# controller.net
KiCad netlist of a schematic drawn in EAGLE
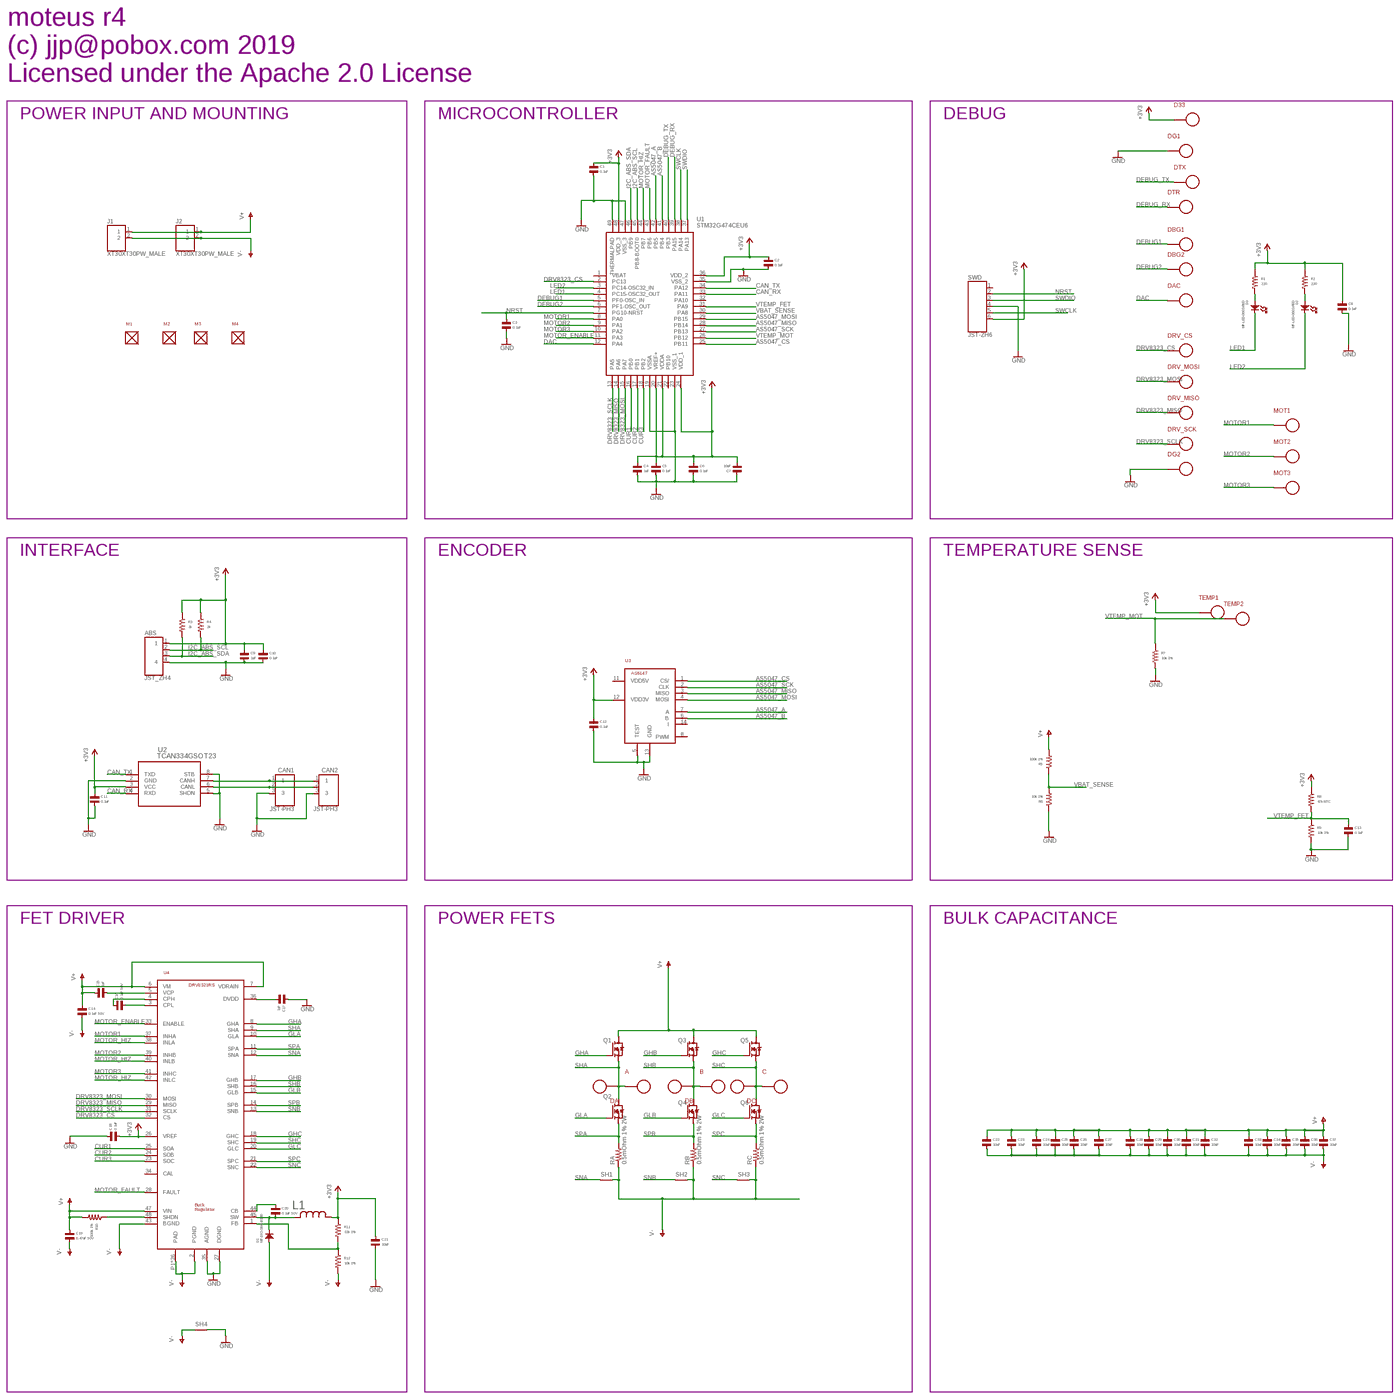
[diagram p0: schematic, sheet 1, overview]
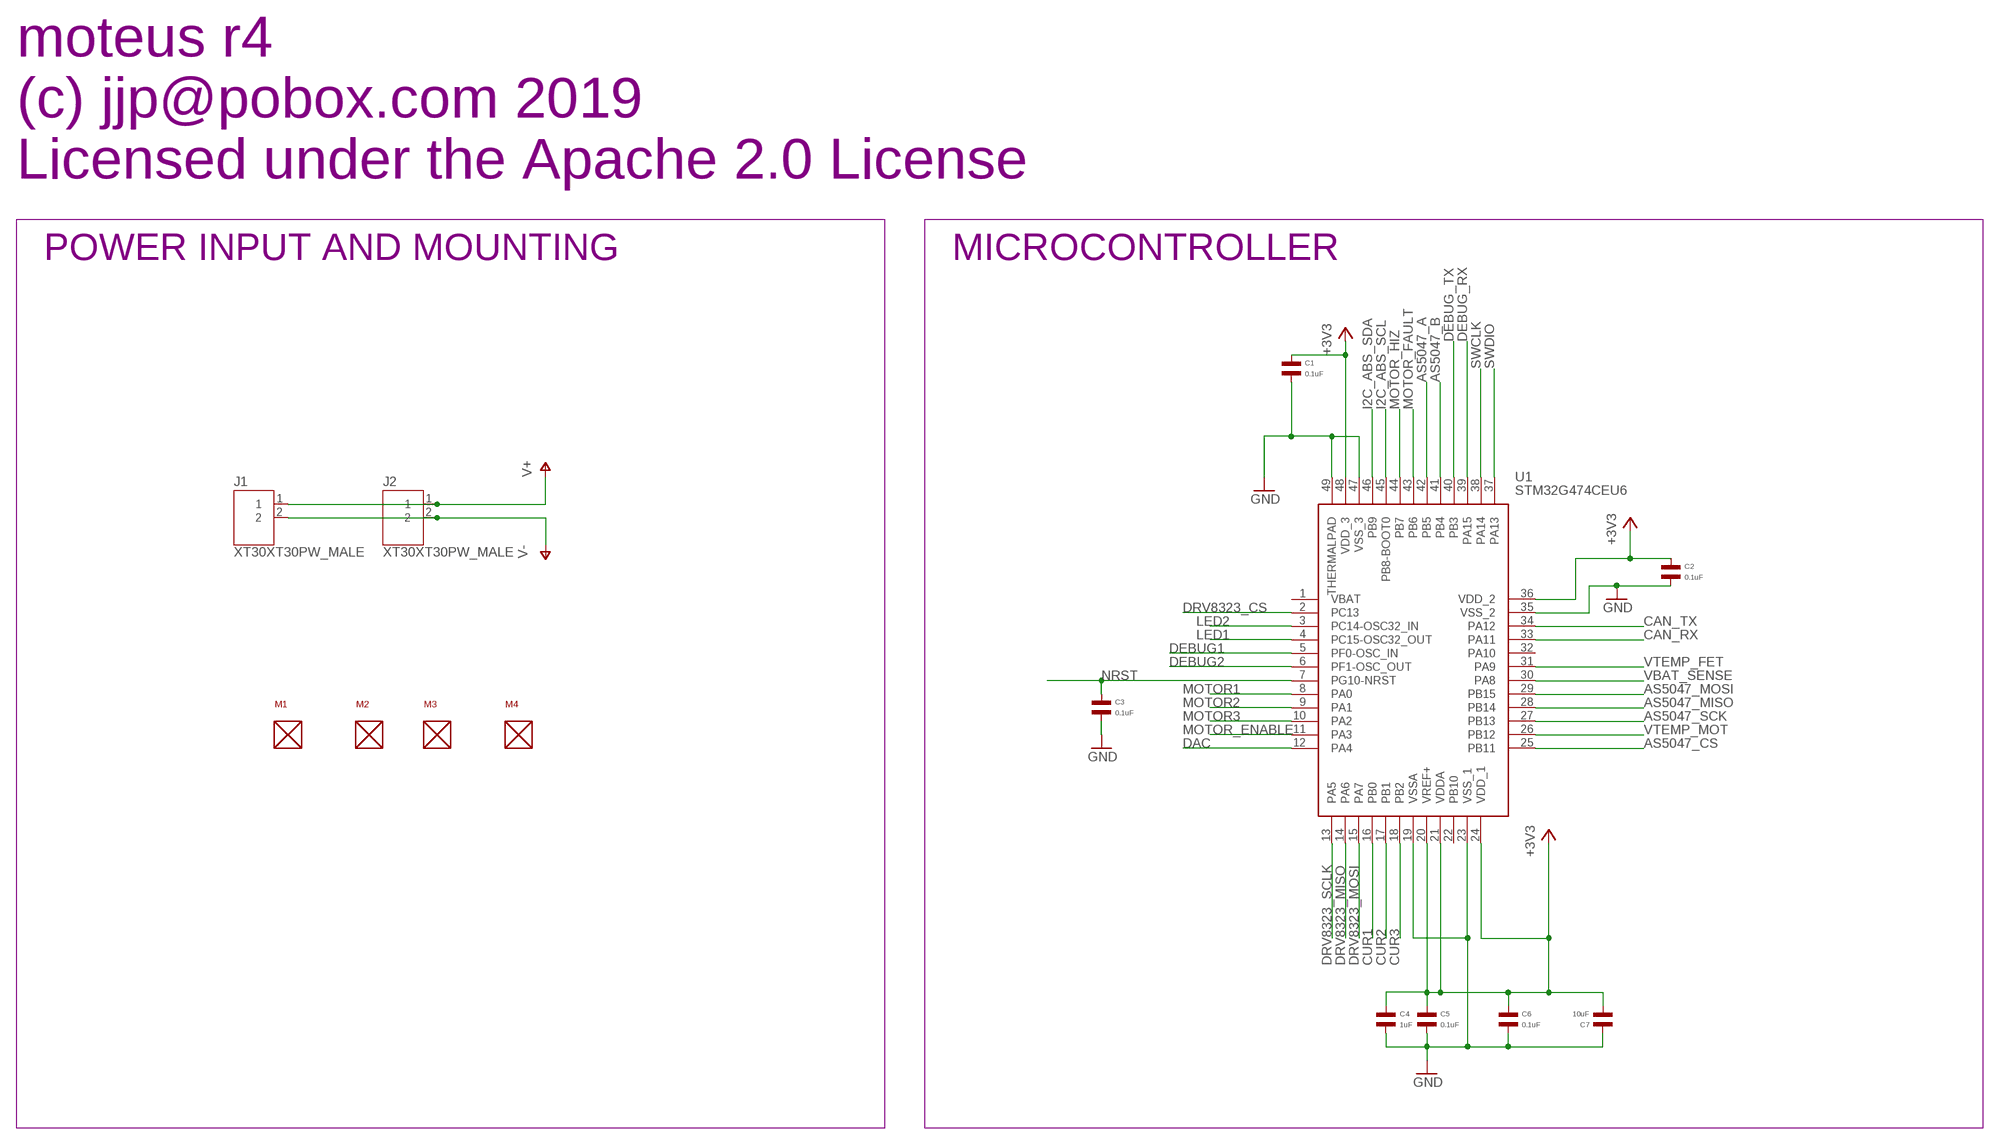
[diagram p1: schematic, sheet 1, part 1 of 4]
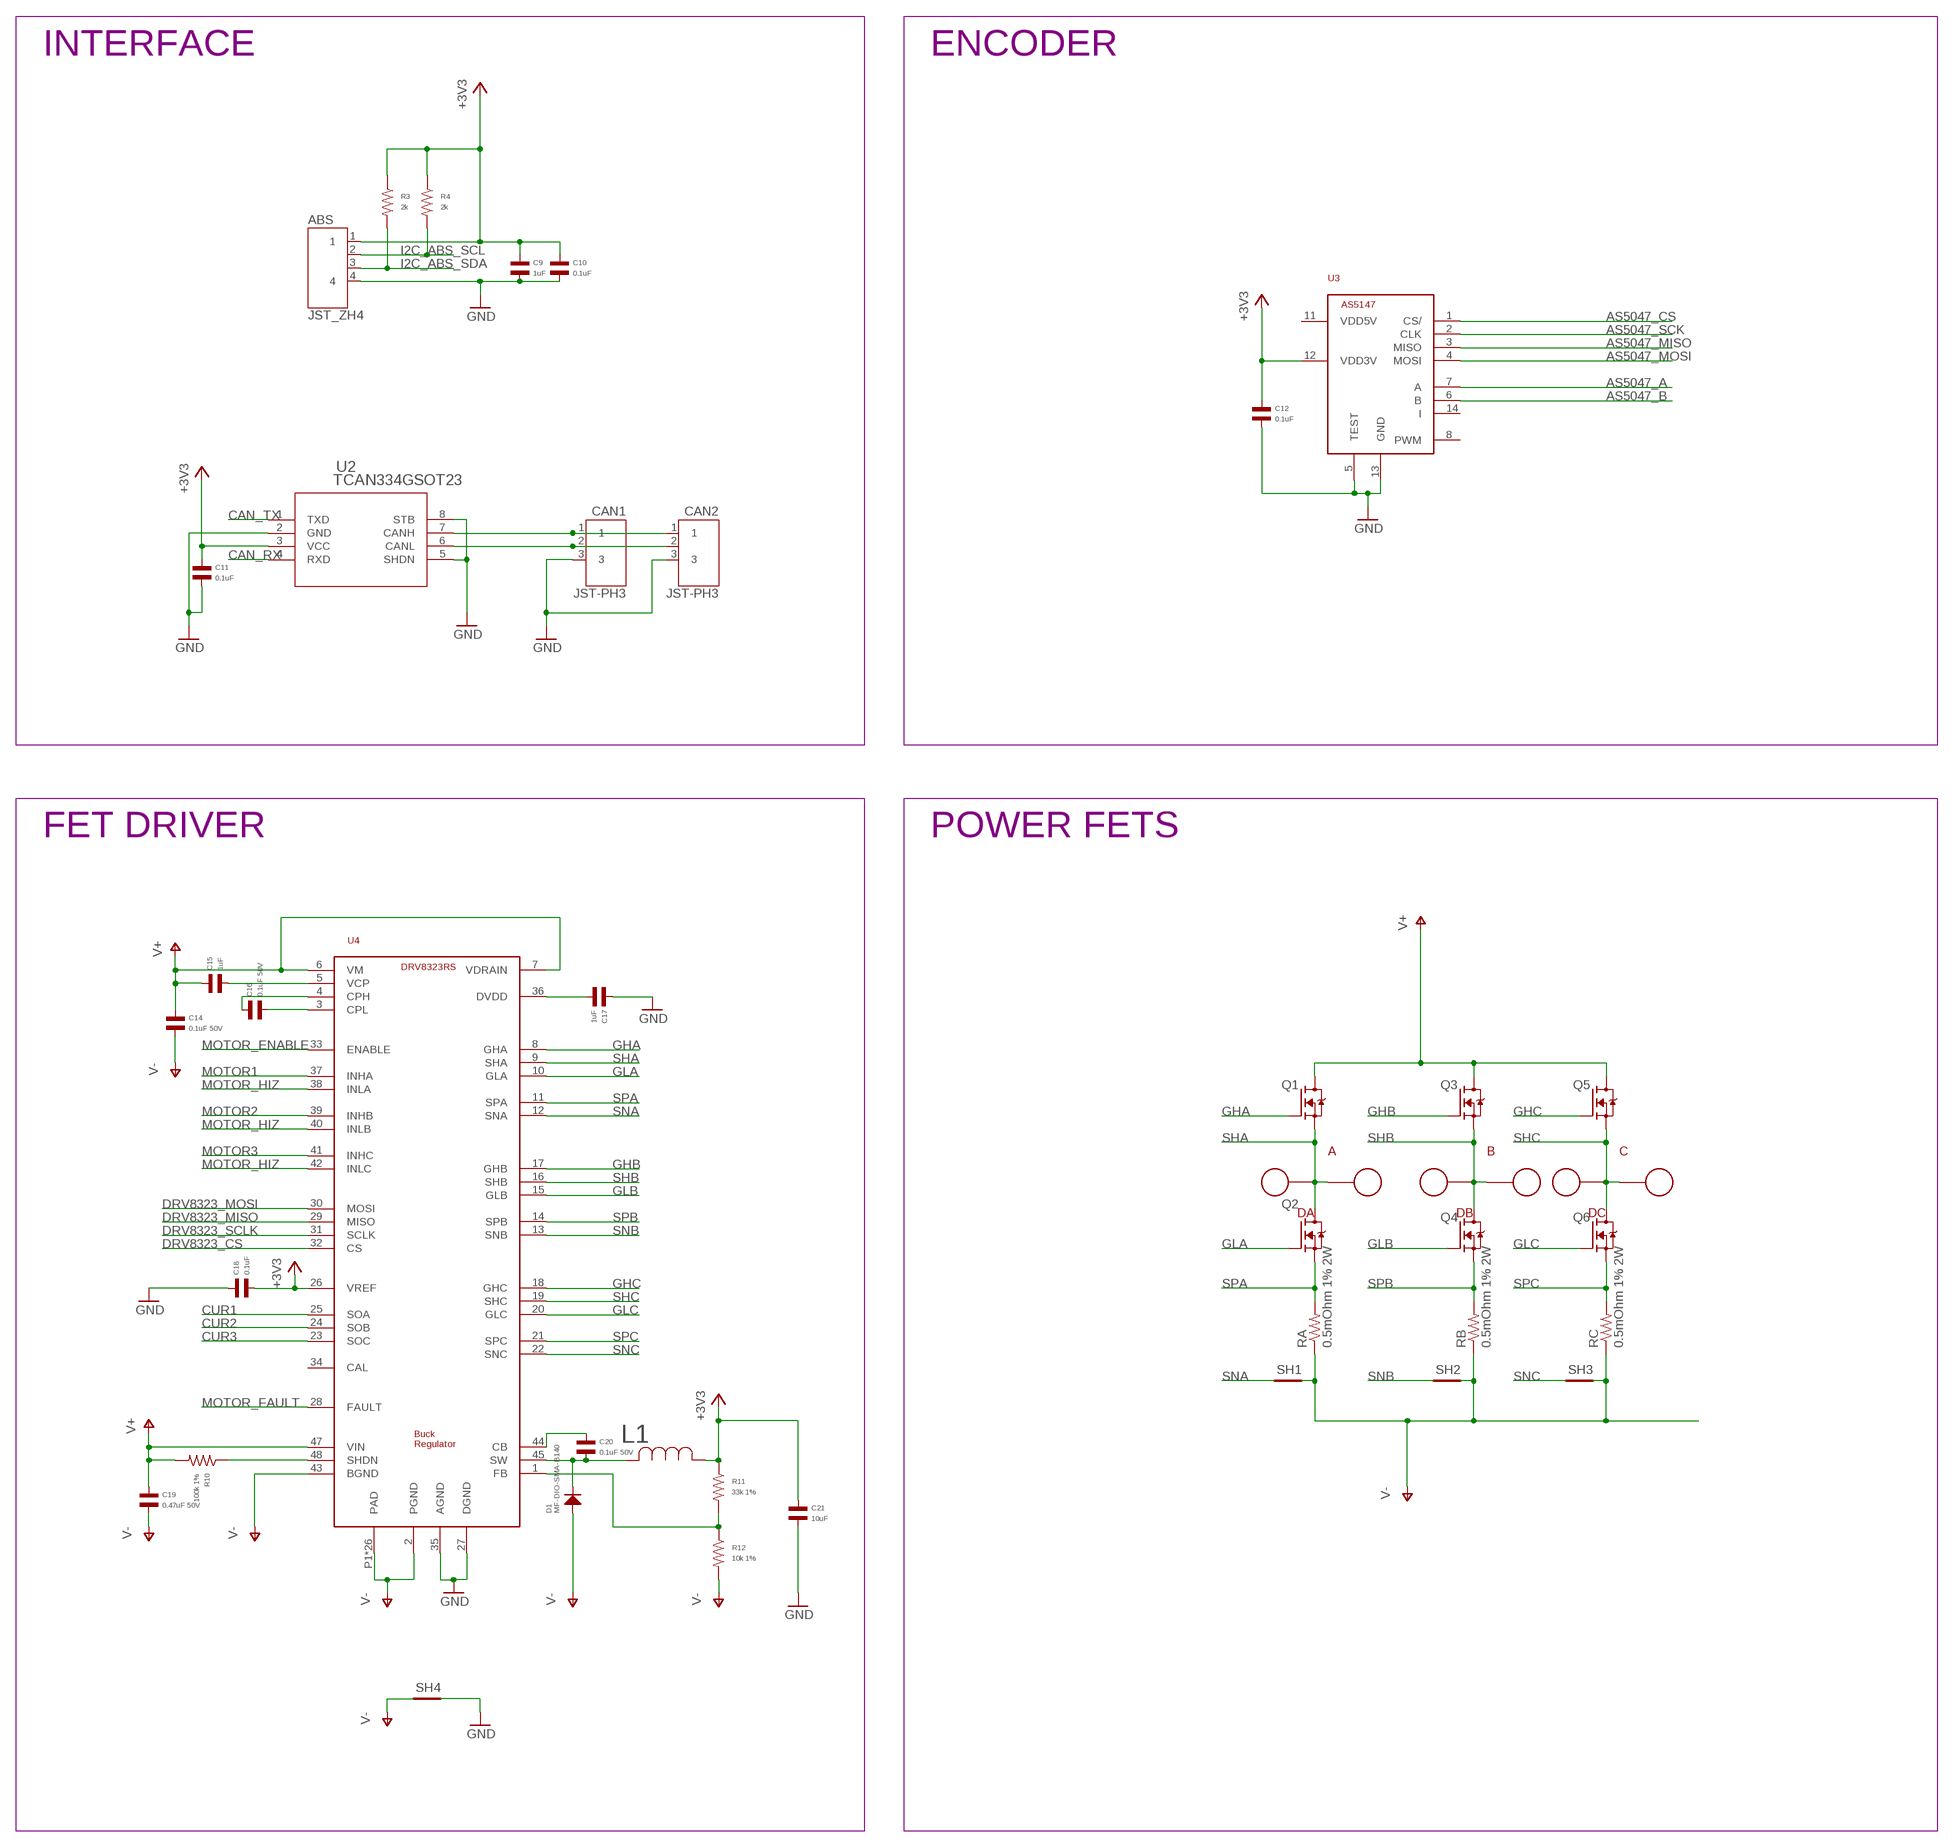
[diagram p2: schematic, sheet 1, part 2 of 4]
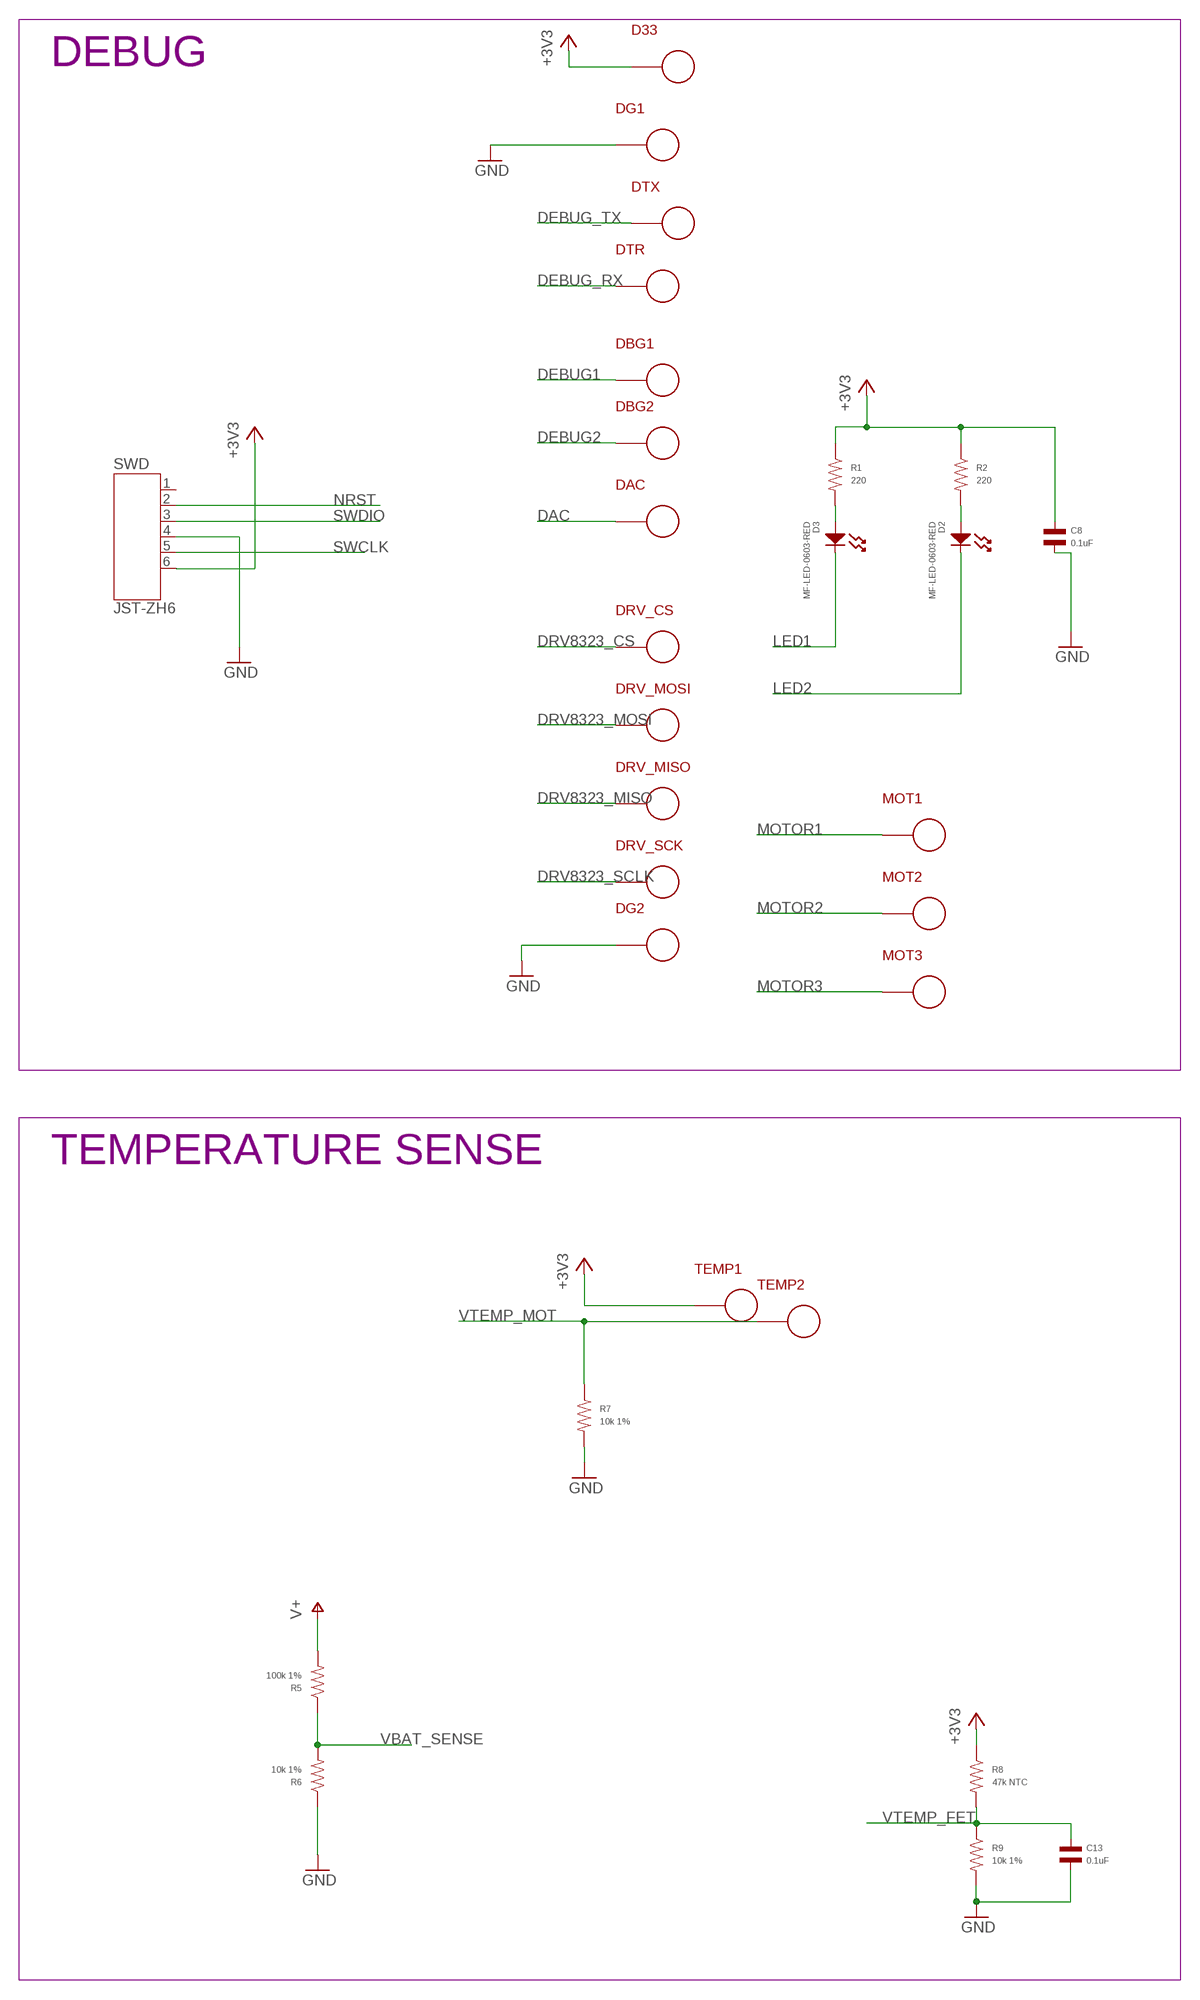
[diagram p3: schematic, sheet 1, part 3 of 4]
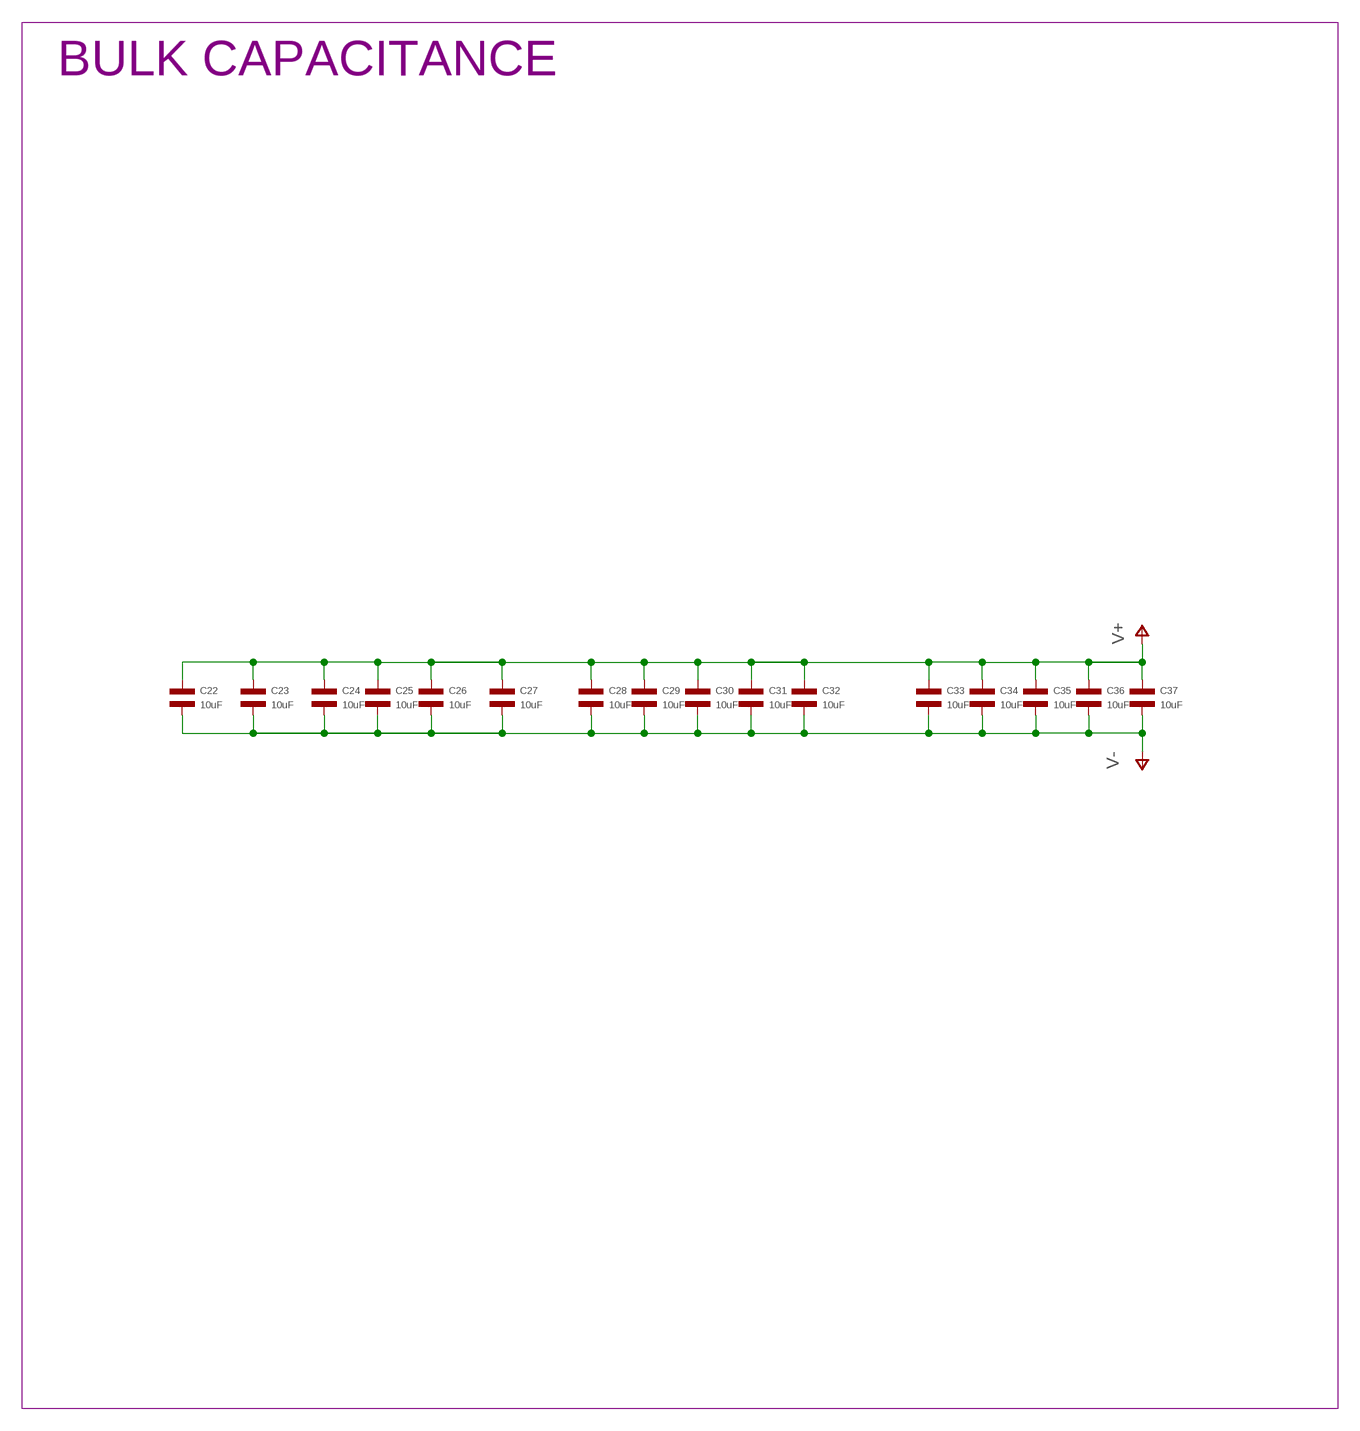
[diagram p4: schematic, sheet 1, part 4 of 4]

(export (version "E")
  (design (tool "Eeschema 10.0.6"))
  (components
    (comp (ref "A")
      (value "PAD")
      (footprint "eagle-import:18AWG_PAD")
      (libsource (lib "eagle-import") (part "PAD"))
    )
    (comp (ref "ABS")
      (value "JST_ZH4")
      (footprint "eagle-import:JST_S4B-ZR-SM4A-TF(LF)(SN)")
      (fields (field (name "MF") "JST") (field (name "MPN") "S4B-ZR-SM4A-TF(LF)(SN)"))
      (libsource (lib "eagle-import") (part "JST_ZH4"))
    )
    (comp (ref "B")
      (value "PAD")
      (footprint "eagle-import:18AWG_PAD")
      (libsource (lib "eagle-import") (part "PAD"))
    )
    (comp (ref "C")
      (value "PAD")
      (footprint "eagle-import:18AWG_PAD")
      (libsource (lib "eagle-import") (part "PAD"))
    )
    (comp (ref "C1")
      (value "0.1uF")
      (footprint "eagle-import:C0402")
      (fields (field (name "HOUSEPART") "YES") (field (name "MPN") "MF-CAP-0402-0.1uF"))
      (libsource (lib "eagle-import") (part "CAPACITOR_NP_0402"))
    )
    (comp (ref "C2")
      (value "0.1uF")
      (footprint "eagle-import:C0402")
      (fields (field (name "HOUSEPART") "YES") (field (name "MPN") "MF-CAP-0402-0.1uF"))
      (libsource (lib "eagle-import") (part "CAPACITOR_NP_0402"))
    )
    (comp (ref "C3")
      (value "0.1uF")
      (footprint "eagle-import:C0402")
      (fields (field (name "HOUSEPART") "YES") (field (name "MPN") "MF-CAP-0402-0.1uF"))
      (libsource (lib "eagle-import") (part "CAPACITOR_NP_0402"))
    )
    (comp (ref "C4")
      (value "1uF")
      (footprint "eagle-import:C0402")
      (fields (field (name "HOUSEPART") "YES") (field (name "MPN") "MF-CAP-0402-1uF"))
      (libsource (lib "eagle-import") (part "CAPACITOR_NP_0402"))
    )
    (comp (ref "C5")
      (value "0.1uF")
      (footprint "eagle-import:C0402")
      (fields (field (name "HOUSEPART") "YES") (field (name "MPN") "MF-CAP-0402-0.1uF"))
      (libsource (lib "eagle-import") (part "CAPACITOR_NP_0402"))
    )
    (comp (ref "C6")
      (value "0.1uF")
      (footprint "eagle-import:C0402")
      (fields (field (name "HOUSEPART") "YES") (field (name "MPN") "MF-CAP-0402-0.1uF"))
      (libsource (lib "eagle-import") (part "CAPACITOR_NP_0402"))
    )
    (comp (ref "C7")
      (value "10uF")
      (footprint "eagle-import:C1206")
      (fields (field (name "HOUSEPART") "YES") (field (name "MPN") "MF-CAP-1206-10uF"))
      (libsource (lib "eagle-import") (part "CAPACITOR_NP_1206"))
    )
    (comp (ref "C8")
      (value "0.1uF")
      (footprint "eagle-import:C0402")
      (fields (field (name "HOUSEPART") "YES") (field (name "MPN") "MF-CAP-0402-0.1uF"))
      (libsource (lib "eagle-import") (part "CAPACITOR_NP_0402"))
    )
    (comp (ref "C9")
      (value "1uF")
      (footprint "eagle-import:C0402")
      (fields (field (name "HOUSEPART") "YES") (field (name "MPN") "MF-CAP-0402-1uF"))
      (libsource (lib "eagle-import") (part "CAPACITOR_NP_0402"))
    )
    (comp (ref "C10")
      (value "0.1uF")
      (footprint "eagle-import:C0402")
      (fields (field (name "HOUSEPART") "YES") (field (name "MPN") "MF-CAP-0402-0.1uF"))
      (libsource (lib "eagle-import") (part "CAPACITOR_NP_0402"))
    )
    (comp (ref "C11")
      (value "0.1uF")
      (footprint "eagle-import:C0402")
      (fields (field (name "HOUSEPART") "YES") (field (name "MPN") "MF-CAP-0402-0.1uF"))
      (libsource (lib "eagle-import") (part "CAPACITOR_NP_0402"))
    )
    (comp (ref "C12")
      (value "0.1uF")
      (footprint "eagle-import:C0402")
      (fields (field (name "HOUSEPART") "YES") (field (name "MPN") "MF-CAP-0402-0.1uF"))
      (libsource (lib "eagle-import") (part "CAPACITOR_NP_0402"))
    )
    (comp (ref "C13")
      (value "0.1uF")
      (footprint "eagle-import:C0402")
      (fields (field (name "HOUSEPART") "YES") (field (name "MPN") "MF-CAP-0402-0.1uF"))
      (libsource (lib "eagle-import") (part "CAPACITOR_NP_0402"))
    )
    (comp (ref "C14")
      (value "0.1uF 50V")
      (footprint "eagle-import:C0402")
      (fields (field (name "MF") "TDK") (field (name "MPN") "CGA2B3X7R1H104K050BB"))
      (libsource (lib "eagle-import") (part "CAPACITOR_NP_0402"))
    )
    (comp (ref "C15")
      (value "1uF")
      (footprint "eagle-import:C0402")
      (fields (field (name "HOUSEPART") "YES") (field (name "MPN") "MF-CAP-0402-1uF"))
      (libsource (lib "eagle-import") (part "CAPACITOR_NP_0402"))
    )
    (comp (ref "C16")
      (value "0.1uF 50V")
      (footprint "eagle-import:C0402")
      (fields (field (name "MF") "TDK") (field (name "MPN") "CGA2B3X7R1H104K050BB"))
      (libsource (lib "eagle-import") (part "CAPACITOR_NP_0402"))
    )
    (comp (ref "C17")
      (value "1uF")
      (footprint "eagle-import:C0402")
      (fields (field (name "HOUSEPART") "YES") (field (name "MPN") "MF-CAP-0402-1uF"))
      (libsource (lib "eagle-import") (part "CAPACITOR_NP_0402"))
    )
    (comp (ref "C18")
      (value "0.1uF")
      (footprint "eagle-import:C0402")
      (fields (field (name "HOUSEPART") "YES") (field (name "MPN") "MF-CAP-0402-0.1uF"))
      (libsource (lib "eagle-import") (part "CAPACITOR_NP_0402"))
    )
    (comp (ref "C19")
      (value "0.47uF 50V")
      (footprint "eagle-import:C0402")
      (fields (field (name "MF") "Taiyo Yuden") (field (name "MPN") "UMK105ABJ474KV-F"))
      (libsource (lib "eagle-import") (part "CAPACITOR_NP_0402"))
    )
    (comp (ref "C20")
      (value "0.1uF 50V")
      (footprint "eagle-import:C0402")
      (fields (field (name "MF") "TDK") (field (name "MPN") "CGA2B3X7R1H104K050BB"))
      (libsource (lib "eagle-import") (part "CAPACITOR_NP_0402"))
    )
    (comp (ref "C21")
      (value "10uF")
      (footprint "eagle-import:C1206")
      (fields (field (name "HOUSEPART") "YES") (field (name "MPN") "MF-CAP-1206-10uF"))
      (libsource (lib "eagle-import") (part "CAPACITOR_NP_1206"))
    )
    (comp (ref "C22")
      (value "10uF")
      (footprint "eagle-import:C1206")
      (fields (field (name "MF") "TDK") (field (name "MPN") "CGA5L1X7R1H106K160AC"))
      (libsource (lib "eagle-import") (part "CAPACITOR_NP_1206"))
    )
    (comp (ref "C23")
      (value "10uF")
      (footprint "eagle-import:C1206")
      (fields (field (name "MF") "TDK") (field (name "MPN") "CGA5L1X7R1H106K160AC"))
      (libsource (lib "eagle-import") (part "CAPACITOR_NP_1206"))
    )
    (comp (ref "C24")
      (value "10uF")
      (footprint "eagle-import:C1206")
      (fields (field (name "MF") "TDK") (field (name "MPN") "CGA5L1X7R1H106K160AC"))
      (libsource (lib "eagle-import") (part "CAPACITOR_NP_1206"))
    )
    (comp (ref "C25")
      (value "10uF")
      (footprint "eagle-import:C1206")
      (fields (field (name "MF") "TDK") (field (name "MPN") "CGA5L1X7R1H106K160AC"))
      (libsource (lib "eagle-import") (part "CAPACITOR_NP_1206"))
    )
    (comp (ref "C26")
      (value "10uF")
      (footprint "eagle-import:C1206")
      (fields (field (name "MF") "TDK") (field (name "MPN") "CGA5L1X7R1H106K160AC"))
      (libsource (lib "eagle-import") (part "CAPACITOR_NP_1206"))
    )
    (comp (ref "C27")
      (value "10uF")
      (footprint "eagle-import:C1206")
      (fields (field (name "MF") "TDK") (field (name "MPN") "CGA5L1X7R1H106K160AC"))
      (libsource (lib "eagle-import") (part "CAPACITOR_NP_1206"))
    )
    (comp (ref "C28")
      (value "10uF")
      (footprint "eagle-import:C1206")
      (fields (field (name "MF") "TDK") (field (name "MPN") "CGA5L1X7R1H106K160AC"))
      (libsource (lib "eagle-import") (part "CAPACITOR_NP_1206"))
    )
    (comp (ref "C29")
      (value "10uF")
      (footprint "eagle-import:C1206")
      (fields (field (name "MF") "TDK") (field (name "MPN") "CGA5L1X7R1H106K160AC"))
      (libsource (lib "eagle-import") (part "CAPACITOR_NP_1206"))
    )
    (comp (ref "C30")
      (value "10uF")
      (footprint "eagle-import:C1206")
      (fields (field (name "MF") "TDK") (field (name "MPN") "CGA5L1X7R1H106K160AC"))
      (libsource (lib "eagle-import") (part "CAPACITOR_NP_1206"))
    )
    (comp (ref "C31")
      (value "10uF")
      (footprint "eagle-import:C1206")
      (fields (field (name "MF") "TDK") (field (name "MPN") "CGA5L1X7R1H106K160AC"))
      (libsource (lib "eagle-import") (part "CAPACITOR_NP_1206"))
    )
    (comp (ref "C32")
      (value "10uF")
      (footprint "eagle-import:C1206")
      (fields (field (name "MF") "TDK") (field (name "MPN") "CGA5L1X7R1H106K160AC"))
      (libsource (lib "eagle-import") (part "CAPACITOR_NP_1206"))
    )
    (comp (ref "C33")
      (value "10uF")
      (footprint "eagle-import:C1206")
      (fields (field (name "MF") "TDK") (field (name "MPN") "CGA5L1X7R1H106K160AC"))
      (libsource (lib "eagle-import") (part "CAPACITOR_NP_1206"))
    )
    (comp (ref "C34")
      (value "10uF")
      (footprint "eagle-import:C1206")
      (fields (field (name "MF") "TDK") (field (name "MPN") "CGA5L1X7R1H106K160AC"))
      (libsource (lib "eagle-import") (part "CAPACITOR_NP_1206"))
    )
    (comp (ref "C35")
      (value "10uF")
      (footprint "eagle-import:C1206")
      (fields (field (name "MF") "TDK") (field (name "MPN") "CGA5L1X7R1H106K160AC"))
      (libsource (lib "eagle-import") (part "CAPACITOR_NP_1206"))
    )
    (comp (ref "C36")
      (value "10uF")
      (footprint "eagle-import:C1206")
      (fields (field (name "MF") "TDK") (field (name "MPN") "CGA5L1X7R1H106K160AC"))
      (libsource (lib "eagle-import") (part "CAPACITOR_NP_1206"))
    )
    (comp (ref "C37")
      (value "10uF")
      (footprint "eagle-import:C1206")
      (fields (field (name "MF") "TDK") (field (name "MPN") "CGA5L1X7R1H106K160AC"))
      (libsource (lib "eagle-import") (part "CAPACITOR_NP_1206"))
    )
    (comp (ref "CAN1")
      (value "JST-PH3")
      (footprint "eagle-import:JST_S3B-PH-SM4-TB(LF)(SN)")
      (fields (field (name "MF") "JST") (field (name "MPN") "S3B-PH-SM4-TB(LF)(SN)"))
      (libsource (lib "eagle-import") (part "JST-PH3"))
    )
    (comp (ref "CAN2")
      (value "JST-PH3")
      (footprint "eagle-import:JST_S3B-PH-SM4-TB(LF)(SN)")
      (fields (field (name "MF") "JST") (field (name "MPN") "S3B-PH-SM4-TB(LF)(SN)"))
      (libsource (lib "eagle-import") (part "JST-PH3"))
    )
    (comp (ref "D1")
      (value "MF-DIO-SMA-B140")
      (footprint "eagle-import:SMA")
      (fields (field (name "HOUSEPART") "YES"))
      (libsource (lib "eagle-import") (part "DIODES_SMA_B140"))
    )
    (comp (ref "D2")
      (value "MF-LED-0603-RED")
      (footprint "eagle-import:LED0603")
      (fields (field (name "HOUSEPART") "YES") (field (name "MPN") "MF-LED-0603-GREEN"))
      (libsource (lib "eagle-import") (part "LED_SINGLE-0603-RED"))
    )
    (comp (ref "D3")
      (value "MF-LED-0603-RED")
      (footprint "eagle-import:LED0603")
      (fields (field (name "HOUSEPART") "YES"))
      (libsource (lib "eagle-import") (part "LED_SINGLE-0603-RED"))
    )
    (comp (ref "D33")
      (value "PAD24AWG_PAD")
      (footprint "eagle-import:24AWG_PAD")
      (libsource (lib "eagle-import") (part "PAD24AWG_PAD"))
    )
    (comp (ref "DA")
      (value "PAD24AWG_PAD")
      (footprint "eagle-import:24AWG_PAD")
      (libsource (lib "eagle-import") (part "PAD24AWG_PAD"))
    )
    (comp (ref "DAC")
      (value "PAD24AWG_PAD")
      (footprint "eagle-import:24AWG_PAD")
      (libsource (lib "eagle-import") (part "PAD24AWG_PAD"))
    )
    (comp (ref "DB")
      (value "PAD24AWG_PAD")
      (footprint "eagle-import:24AWG_PAD")
      (libsource (lib "eagle-import") (part "PAD24AWG_PAD"))
    )
    (comp (ref "DBG1")
      (value "PAD24AWG_PAD")
      (footprint "eagle-import:24AWG_PAD")
      (libsource (lib "eagle-import") (part "PAD24AWG_PAD"))
    )
    (comp (ref "DBG2")
      (value "PAD24AWG_PAD")
      (footprint "eagle-import:24AWG_PAD")
      (libsource (lib "eagle-import") (part "PAD24AWG_PAD"))
    )
    (comp (ref "DC")
      (value "PAD24AWG_PAD")
      (footprint "eagle-import:24AWG_PAD")
      (libsource (lib "eagle-import") (part "PAD24AWG_PAD"))
    )
    (comp (ref "DG1")
      (value "PAD24AWG_PAD")
      (footprint "eagle-import:24AWG_PAD")
      (libsource (lib "eagle-import") (part "PAD24AWG_PAD"))
    )
    (comp (ref "DG2")
      (value "PAD24AWG_PAD")
      (footprint "eagle-import:24AWG_PAD")
      (libsource (lib "eagle-import") (part "PAD24AWG_PAD"))
    )
    (comp (ref "DRV_CS")
      (value "PAD24AWG_PAD")
      (footprint "eagle-import:24AWG_PAD")
      (libsource (lib "eagle-import") (part "PAD24AWG_PAD"))
    )
    (comp (ref "DRV_MISO")
      (value "PAD24AWG_PAD")
      (footprint "eagle-import:24AWG_PAD")
      (libsource (lib "eagle-import") (part "PAD24AWG_PAD"))
    )
    (comp (ref "DRV_MOSI")
      (value "PAD24AWG_PAD")
      (footprint "eagle-import:24AWG_PAD")
      (libsource (lib "eagle-import") (part "PAD24AWG_PAD"))
    )
    (comp (ref "DRV_SCK")
      (value "PAD24AWG_PAD")
      (footprint "eagle-import:24AWG_PAD")
      (libsource (lib "eagle-import") (part "PAD24AWG_PAD"))
    )
    (comp (ref "DTR")
      (value "PAD24AWG_PAD")
      (footprint "eagle-import:24AWG_PAD")
      (libsource (lib "eagle-import") (part "PAD24AWG_PAD"))
    )
    (comp (ref "DTX")
      (value "PAD24AWG_PAD")
      (footprint "eagle-import:24AWG_PAD")
      (libsource (lib "eagle-import") (part "PAD24AWG_PAD"))
    )
    (comp (ref "J1")
      (value "XT30XT30PW_MALE")
      (footprint "eagle-import:XT30PW_MALE")
      (libsource (lib "eagle-import") (part "XT30XT30PW_MALE"))
    )
    (comp (ref "J2")
      (value "XT30XT30PW_MALE")
      (footprint "eagle-import:XT30PW_MALE")
      (libsource (lib "eagle-import") (part "XT30XT30PW_MALE"))
    )
    (comp (ref "L1")
      (value "SRN4018-220M")
      (footprint "eagle-import:IND_BOURNS_SRN4018")
      (fields (field (name "MANUFACTURER_PART_NUMBER") "SRN4018220M"))
      (libsource (lib "eagle-import") (part "SRN4018-220M"))
    )
    (comp (ref "M1")
      (value "MOUNT")
      (footprint "eagle-import:M2.5MOUNT")
      (libsource (lib "eagle-import") (part "MOUNT"))
    )
    (comp (ref "M2")
      (value "MOUNT")
      (footprint "eagle-import:M2.5MOUNT")
      (libsource (lib "eagle-import") (part "MOUNT"))
    )
    (comp (ref "M3")
      (value "MOUNT")
      (footprint "eagle-import:M2.5MOUNT")
      (libsource (lib "eagle-import") (part "MOUNT"))
    )
    (comp (ref "M4")
      (value "MOUNT")
      (footprint "eagle-import:M2.5MOUNT")
      (libsource (lib "eagle-import") (part "MOUNT"))
    )
    (comp (ref "MOT1")
      (value "PAD24AWG_PAD")
      (footprint "eagle-import:24AWG_PAD")
      (libsource (lib "eagle-import") (part "PAD24AWG_PAD"))
    )
    (comp (ref "MOT2")
      (value "PAD24AWG_PAD")
      (footprint "eagle-import:24AWG_PAD")
      (libsource (lib "eagle-import") (part "PAD24AWG_PAD"))
    )
    (comp (ref "MOT3")
      (value "PAD24AWG_PAD")
      (footprint "eagle-import:24AWG_PAD")
      (libsource (lib "eagle-import") (part "PAD24AWG_PAD"))
    )
    (comp (ref "Q1")
      (value "TPH1R204PLSOP_ADVANCE_8")
      (footprint "eagle-import:SOP_ADVANCE_8")
      (fields
        (field (name "MF") "Toshiba")
        (field (name "MPN") "TPH1R204PL")
        (field (name "MF_1") "Toshiba")
        (field (name "MPN_1") "TPH1R204PL,L1Q")
      )
      (libsource (lib "eagle-import") (part "TPH1R204PLSOP_ADVANCE_8"))
    )
    (comp (ref "Q2")
      (value "TPH1R204PLSOP_ADVANCE_8")
      (footprint "eagle-import:SOP_ADVANCE_8")
      (fields
        (field (name "MF") "Toshiba")
        (field (name "MPN") "TPH1R204PL")
        (field (name "MF_1") "Toshiba")
        (field (name "MPN_1") "TPH1R204PL,L1Q")
      )
      (libsource (lib "eagle-import") (part "TPH1R204PLSOP_ADVANCE_8"))
    )
    (comp (ref "Q3")
      (value "TPH1R204PLSOP_ADVANCE_8")
      (footprint "eagle-import:SOP_ADVANCE_8")
      (fields
        (field (name "MF") "Toshiba")
        (field (name "MPN") "TPH1R204PL")
        (field (name "MF_1") "Toshiba")
        (field (name "MPN_1") "TPH1R204PL,L1Q")
      )
      (libsource (lib "eagle-import") (part "TPH1R204PLSOP_ADVANCE_8"))
    )
    (comp (ref "Q4")
      (value "TPH1R204PLSOP_ADVANCE_8")
      (footprint "eagle-import:SOP_ADVANCE_8")
      (fields
        (field (name "MF") "Toshiba")
        (field (name "MPN") "TPH1R204PL")
        (field (name "MF_1") "Toshiba")
        (field (name "MPN_1") "TPH1R204PL,L1Q")
      )
      (libsource (lib "eagle-import") (part "TPH1R204PLSOP_ADVANCE_8"))
    )
    (comp (ref "Q5")
      (value "TPH1R204PLSOP_ADVANCE_8")
      (footprint "eagle-import:SOP_ADVANCE_8")
      (fields
        (field (name "MF") "Toshiba")
        (field (name "MPN") "TPH1R204PL")
        (field (name "MF_1") "Toshiba")
        (field (name "MPN_1") "TPH1R204PL,L1Q")
      )
      (libsource (lib "eagle-import") (part "TPH1R204PLSOP_ADVANCE_8"))
    )
    (comp (ref "Q6")
      (value "TPH1R204PLSOP_ADVANCE_8")
      (footprint "eagle-import:SOP_ADVANCE_8")
      (fields
        (field (name "MF") "Toshiba")
        (field (name "MPN") "TPH1R204PL")
        (field (name "MF_1") "Toshiba")
        (field (name "MPN_1") "TPH1R204PL,L1Q")
      )
      (libsource (lib "eagle-import") (part "TPH1R204PLSOP_ADVANCE_8"))
    )
    (comp (ref "R1")
      (value "220")
      (footprint "eagle-import:R0402")
      (fields (field (name "HOUSEPART") "1") (field (name "MPN") "MF-RES-0402-220"))
      (libsource (lib "eagle-import") (part "RESISTOR_0402"))
    )
    (comp (ref "R2")
      (value "220")
      (footprint "eagle-import:R0402")
      (fields (field (name "HOUSEPART") "1") (field (name "MPN") "MF-RES-0402-220"))
      (libsource (lib "eagle-import") (part "RESISTOR_0402"))
    )
    (comp (ref "R3")
      (value "2k")
      (footprint "eagle-import:R0402")
      (fields (field (name "MF") "Panasonic") (field (name "MPN") "ERJ-2RKF1002X"))
      (libsource (lib "eagle-import") (part "RESISTOR_0402"))
    )
    (comp (ref "R4")
      (value "2k")
      (footprint "eagle-import:R0402")
      (fields (field (name "MF") "Panasonic") (field (name "MPN") "ERJ-2RKF1002X"))
      (libsource (lib "eagle-import") (part "RESISTOR_0402"))
    )
    (comp (ref "R5")
      (value "100k 1%")
      (footprint "eagle-import:R0402")
      (fields (field (name "MF") "Panasonic") (field (name "MPN") "ERJ-2RKF1003X"))
      (libsource (lib "eagle-import") (part "RESISTOR_0402"))
    )
    (comp (ref "R6")
      (value "10k 1%")
      (footprint "eagle-import:R0402")
      (fields (field (name "MF") "Panasonic") (field (name "MPN") "ERJ-2RKF1002X"))
      (libsource (lib "eagle-import") (part "RESISTOR_0402"))
    )
    (comp (ref "R7")
      (value "10k 1%")
      (footprint "eagle-import:R0402")
      (fields (field (name "MF") "Panasonic") (field (name "MPN") "ERJ-2RKF1002X"))
      (libsource (lib "eagle-import") (part "RESISTOR_0402"))
    )
    (comp (ref "R8")
      (value "47k NTC")
      (footprint "eagle-import:R0402")
      (fields (field (name "MF") "Murata") (field (name "MPN") "NCP15WB473F03RC"))
      (libsource (lib "eagle-import") (part "RESISTOR_0402"))
    )
    (comp (ref "R9")
      (value "10k 1%")
      (footprint "eagle-import:R0402")
      (fields (field (name "MF") "Panasonic") (field (name "MPN") "ERJ-2RKF1002X"))
      (libsource (lib "eagle-import") (part "RESISTOR_0402"))
    )
    (comp (ref "R10")
      (value "100k 1%")
      (footprint "eagle-import:R0402")
      (fields (field (name "MF") "Panasonic") (field (name "MPN") "ERJ-2RKF1003X"))
      (libsource (lib "eagle-import") (part "RESISTOR_0402"))
    )
    (comp (ref "R11")
      (value "33k 1%")
      (footprint "eagle-import:R0402")
      (fields (field (name "MF") "Panasonic") (field (name "MPN") "ERJ-2RKF3302X"))
      (libsource (lib "eagle-import") (part "RESISTOR_0402"))
    )
    (comp (ref "R12")
      (value "10k 1%")
      (footprint "eagle-import:R0402")
      (fields (field (name "MF") "Panasonic") (field (name "MPN") "ERJ-2RKF1002X"))
      (libsource (lib "eagle-import") (part "RESISTOR_0402"))
    )
    (comp (ref "RA")
      (value "0.5mOhm 1% 2W")
      (footprint "eagle-import:M1206")
      (fields (field (name "MF") "Stackpole Electronics") (field (name "MPN") "HCS1206FTL500"))
      (libsource (lib "eagle-import") (part "R-US_M1206"))
    )
    (comp (ref "RB")
      (value "0.5mOhm 1% 2W")
      (footprint "eagle-import:M1206")
      (fields (field (name "MF") "Stackpole Electronics") (field (name "MPN") "HCS1206FTL500"))
      (libsource (lib "eagle-import") (part "R-US_M1206"))
    )
    (comp (ref "RC")
      (value "0.5mOhm 1% 2W")
      (footprint "eagle-import:M1206")
      (fields (field (name "MF") "Stackpole Electronics") (field (name "MPN") "HCS1206FTL500"))
      (libsource (lib "eagle-import") (part "R-US_M1206"))
    )
    (comp (ref "SH1")
      (value "SHORTT5")
      (footprint "eagle-import:SHORT_TOP-50")
      (libsource (lib "eagle-import") (part "SHORTT5"))
    )
    (comp (ref "SH2")
      (value "SHORTT5")
      (footprint "eagle-import:SHORT_TOP-50")
      (libsource (lib "eagle-import") (part "SHORTT5"))
    )
    (comp (ref "SH3")
      (value "SHORTT5")
      (footprint "eagle-import:SHORT_TOP-50")
      (libsource (lib "eagle-import") (part "SHORTT5"))
    )
    (comp (ref "SH4")
      (value "SHORTBIG")
      (footprint "eagle-import:SHORT_TOP-BIG")
      (libsource (lib "eagle-import") (part "SHORTBIG"))
    )
    (comp (ref "SWD")
      (value "JST-ZH6")
      (footprint "eagle-import:JST_S6B-ZR-SM4A-TF(LF)(SN)")
      (fields (field (name "MF") "JST") (field (name "MPN") "S6B-ZR-SM4A-TF(LF)(SN)"))
      (libsource (lib "eagle-import") (part "JST-ZH6"))
    )
    (comp (ref "TEMP1")
      (value "PAD24AWG_PAD")
      (footprint "eagle-import:24AWG_PAD")
      (libsource (lib "eagle-import") (part "PAD24AWG_PAD"))
    )
    (comp (ref "TEMP2")
      (value "PAD24AWG_PAD")
      (footprint "eagle-import:24AWG_PAD")
      (libsource (lib "eagle-import") (part "PAD24AWG_PAD"))
    )
    (comp (ref "U1")
      (value "STM32G474CEU6")
      (footprint "eagle-import:QFN50P700X700X60-49N")
      (fields (field (name "MOUSER_PART_NUMBER") "511-STM32G474CEU6"))
      (libsource (lib "eagle-import") (part "STM32G474CEU6"))
    )
    (comp (ref "U2")
      (value "TCAN334GSOT23")
      (footprint "eagle-import:SOT23-8")
      (fields (field (name "MF") "TI") (field (name "MPN") "TCAN334GDCNT"))
      (libsource (lib "eagle-import") (part "TCAN334GSOT23"))
    )
    (comp (ref "U3")
      (value "AS5147")
      (footprint "eagle-import:TSSOP14")
      (fields (field (name "MF") "AMS") (field (name "MPN") "AS5047P-ATSM"))
      (libsource (lib "eagle-import") (part "AS5147"))
    )
    (comp (ref "U4")
      (value "DRV8323RS")
      (footprint "eagle-import:PVQFN-N48")
      (fields (field (name "MF") "TI") (field (name "MPN") "DRV8323RSRGZR"))
      (libsource (lib "eagle-import") (part "DRV8323RS"))
    )
  )
  (nets
    (net (code "1") (name "+3V3") (class "Default")
      (node (ref "ABS") (pin "1") (pinfunction "1_1") (pintype "passive"))
      (node (ref "C1") (pin "P$1") (pinfunction "P$1_P$1") (pintype "passive"))
      (node (ref "C10") (pin "P$1") (pinfunction "P$1_P$1") (pintype "passive"))
      (node (ref "C11") (pin "P$1") (pinfunction "P$1_P$1") (pintype "passive"))
      (node (ref "C12") (pin "P$1") (pinfunction "P$1_P$1") (pintype "passive"))
      (node (ref "C18") (pin "P$2") (pinfunction "P$2_P$2") (pintype "passive"))
      (node (ref "C2") (pin "P$1") (pinfunction "P$1_P$1") (pintype "passive"))
      (node (ref "C21") (pin "P$1") (pinfunction "P$1_P$1") (pintype "passive"))
      (node (ref "C4") (pin "P$1") (pinfunction "P$1_P$1") (pintype "passive"))
      (node (ref "C5") (pin "P$1") (pinfunction "P$1_P$1") (pintype "passive"))
      (node (ref "C6") (pin "P$1") (pinfunction "P$1_P$1") (pintype "passive"))
      (node (ref "C7") (pin "P$2") (pinfunction "P$2_P$2") (pintype "passive"))
      (node (ref "C8") (pin "P$1") (pinfunction "P$1_P$1") (pintype "passive"))
      (node (ref "C9") (pin "P$1") (pinfunction "P$1_P$1") (pintype "passive"))
      (node (ref "D33") (pin "P$1") (pinfunction "P$1_P$1") (pintype "bidirectional"))
      (node (ref "L1") (pin "1") (pinfunction "1_1") (pintype "passive"))
      (node (ref "R1") (pin "P$1") (pinfunction "P$1_P$1") (pintype "passive"))
      (node (ref "R11") (pin "P$1") (pinfunction "P$1_P$1") (pintype "passive"))
      (node (ref "R2") (pin "P$1") (pinfunction "P$1_P$1") (pintype "passive"))
      (node (ref "R3") (pin "P$1") (pinfunction "P$1_P$1") (pintype "passive"))
      (node (ref "R4") (pin "P$1") (pinfunction "P$1_P$1") (pintype "passive"))
      (node (ref "R8") (pin "P$1") (pinfunction "P$1_P$1") (pintype "passive"))
      (node (ref "SWD") (pin "6") (pinfunction "6_6") (pintype "passive"))
      (node (ref "TEMP1") (pin "P$1") (pinfunction "P$1_P$1") (pintype "bidirectional"))
      (node (ref "U1") (pin "20") (pinfunction "VREF+_20") (pintype "bidirectional"))
      (node (ref "U1") (pin "21") (pinfunction "VDDA_21") (pintype "bidirectional"))
      (node (ref "U1") (pin "24") (pinfunction "VDD_1_24") (pintype "bidirectional"))
      (node (ref "U1") (pin "36") (pinfunction "VDD_2_36") (pintype "bidirectional"))
      (node (ref "U1") (pin "48") (pinfunction "VDD_3_48") (pintype "bidirectional"))
      (node (ref "U2") (pin "3") (pinfunction "VCC_3") (pintype "power_in"))
      (node (ref "U3") (pin "12") (pinfunction "VDD3V_12") (pintype "bidirectional"))
      (node (ref "U4") (pin "26") (pinfunction "VREF_26") (pintype "bidirectional"))
    )
    (net (code "2") (name "/AS5047_A") (class "Default")
      (node (ref "U1") (pin "42") (pinfunction "PB5_42") (pintype "bidirectional"))
      (node (ref "U3") (pin "7") (pinfunction "A_7") (pintype "bidirectional"))
    )
    (net (code "3") (name "/AS5047_B") (class "Default")
      (node (ref "U1") (pin "41") (pinfunction "PB4_41") (pintype "bidirectional"))
      (node (ref "U3") (pin "6") (pinfunction "B_6") (pintype "bidirectional"))
    )
    (net (code "4") (name "/AS5047_CS") (class "Default")
      (node (ref "U1") (pin "25") (pinfunction "PB11_25") (pintype "bidirectional"))
      (node (ref "U3") (pin "1") (pinfunction "CS/_1") (pintype "bidirectional"))
    )
    (net (code "5") (name "/AS5047_MISO") (class "Default")
      (node (ref "U1") (pin "28") (pinfunction "PB14_28") (pintype "bidirectional"))
      (node (ref "U3") (pin "3") (pinfunction "MISO_3") (pintype "bidirectional"))
    )
    (net (code "6") (name "/AS5047_MOSI") (class "Default")
      (node (ref "U1") (pin "29") (pinfunction "PB15_29") (pintype "bidirectional"))
      (node (ref "U3") (pin "4") (pinfunction "MOSI_4") (pintype "bidirectional"))
    )
    (net (code "7") (name "/AS5047_SCK") (class "Default")
      (node (ref "U1") (pin "27") (pinfunction "PB13_27") (pintype "bidirectional"))
      (node (ref "U3") (pin "2") (pinfunction "CLK_2") (pintype "bidirectional"))
    )
    (net (code "8") (name "/CAN_RX") (class "Default")
      (node (ref "U1") (pin "33") (pinfunction "PA11_33") (pintype "bidirectional"))
      (node (ref "U2") (pin "4") (pinfunction "RXD_4") (pintype "output"))
    )
    (net (code "9") (name "/CAN_TX") (class "Default")
      (node (ref "U1") (pin "34") (pinfunction "PA12_34") (pintype "bidirectional"))
      (node (ref "U2") (pin "1") (pinfunction "TXD_1") (pintype "input"))
    )
    (net (code "10") (name "/CUR1") (class "Default")
      (node (ref "U1") (pin "16") (pinfunction "PB0_16") (pintype "bidirectional"))
      (node (ref "U4") (pin "25") (pinfunction "SOA_25") (pintype "bidirectional"))
    )
    (net (code "11") (name "/CUR2") (class "Default")
      (node (ref "U1") (pin "17") (pinfunction "PB1_17") (pintype "bidirectional"))
      (node (ref "U4") (pin "24") (pinfunction "SOB_24") (pintype "bidirectional"))
    )
    (net (code "12") (name "/CUR3") (class "Default")
      (node (ref "U1") (pin "18") (pinfunction "PB2_18") (pintype "bidirectional"))
      (node (ref "U4") (pin "23") (pinfunction "SOC_23") (pintype "bidirectional"))
    )
    (net (code "13") (name "/DAC") (class "Default")
      (node (ref "DAC") (pin "P$1") (pinfunction "P$1_P$1") (pintype "bidirectional"))
      (node (ref "U1") (pin "12") (pinfunction "PA4_12") (pintype "bidirectional"))
    )
    (net (code "14") (name "/DEBUG1") (class "Default")
      (node (ref "DBG1") (pin "P$1") (pinfunction "P$1_P$1") (pintype "bidirectional"))
      (node (ref "U1") (pin "5") (pinfunction "PF0-OSC_IN_5") (pintype "bidirectional"))
    )
    (net (code "15") (name "/DEBUG2") (class "Default")
      (node (ref "DBG2") (pin "P$1") (pinfunction "P$1_P$1") (pintype "bidirectional"))
      (node (ref "U1") (pin "6") (pinfunction "PF1-OSC_OUT_6") (pintype "bidirectional"))
    )
    (net (code "16") (name "/DEBUG_RX") (class "Default")
      (node (ref "DTR") (pin "P$1") (pinfunction "P$1_P$1") (pintype "bidirectional"))
      (node (ref "U1") (pin "39") (pinfunction "PA15_39") (pintype "bidirectional"))
    )
    (net (code "17") (name "/DEBUG_TX") (class "Default")
      (node (ref "DTX") (pin "P$1") (pinfunction "P$1_P$1") (pintype "bidirectional"))
      (node (ref "U1") (pin "40") (pinfunction "PB3_40") (pintype "bidirectional"))
    )
    (net (code "18") (name "/DRV8323_CS") (class "Default")
      (node (ref "DRV_CS") (pin "P$1") (pinfunction "P$1_P$1") (pintype "bidirectional"))
      (node (ref "U1") (pin "2") (pinfunction "PC13_2") (pintype "bidirectional"))
      (node (ref "U4") (pin "32") (pinfunction "CS_32") (pintype "bidirectional"))
    )
    (net (code "19") (name "/DRV8323_MISO") (class "Default")
      (node (ref "DRV_MISO") (pin "P$1") (pinfunction "P$1_P$1") (pintype "bidirectional"))
      (node (ref "U1") (pin "14") (pinfunction "PA6_14") (pintype "bidirectional"))
      (node (ref "U4") (pin "29") (pinfunction "MISO_29") (pintype "bidirectional"))
    )
    (net (code "20") (name "/DRV8323_MOSI") (class "Default")
      (node (ref "DRV_MOSI") (pin "P$1") (pinfunction "P$1_P$1") (pintype "bidirectional"))
      (node (ref "U1") (pin "15") (pinfunction "PA7_15") (pintype "bidirectional"))
      (node (ref "U4") (pin "30") (pinfunction "MOSI_30") (pintype "bidirectional"))
    )
    (net (code "21") (name "/DRV8323_SCLK") (class "Default")
      (node (ref "DRV_SCK") (pin "P$1") (pinfunction "P$1_P$1") (pintype "bidirectional"))
      (node (ref "U1") (pin "13") (pinfunction "PA5_13") (pintype "bidirectional"))
      (node (ref "U4") (pin "31") (pinfunction "SCLK_31") (pintype "bidirectional"))
    )
    (net (code "22") (name "/GHA") (class "Default")
      (node (ref "Q1") (pin "4") (pinfunction "G_4") (pintype "passive"))
      (node (ref "U4") (pin "8") (pinfunction "GHA_8") (pintype "bidirectional"))
    )
    (net (code "23") (name "/GHB") (class "Default")
      (node (ref "Q3") (pin "4") (pinfunction "G_4") (pintype "passive"))
      (node (ref "U4") (pin "17") (pinfunction "GHB_17") (pintype "bidirectional"))
    )
    (net (code "24") (name "/GHC") (class "Default")
      (node (ref "Q5") (pin "4") (pinfunction "G_4") (pintype "passive"))
      (node (ref "U4") (pin "18") (pinfunction "GHC_18") (pintype "bidirectional"))
    )
    (net (code "25") (name "/GLA") (class "Default")
      (node (ref "Q2") (pin "4") (pinfunction "G_4") (pintype "passive"))
      (node (ref "U4") (pin "10") (pinfunction "GLA_10") (pintype "bidirectional"))
    )
    (net (code "26") (name "/GLB") (class "Default")
      (node (ref "Q4") (pin "4") (pinfunction "G_4") (pintype "passive"))
      (node (ref "U4") (pin "15") (pinfunction "GLB_15") (pintype "bidirectional"))
    )
    (net (code "27") (name "/GLC") (class "Default")
      (node (ref "Q6") (pin "4") (pinfunction "G_4") (pintype "passive"))
      (node (ref "U4") (pin "20") (pinfunction "GLC_20") (pintype "bidirectional"))
    )
    (net (code "28") (name "/I2C_ABS_SCL") (class "Default")
      (node (ref "ABS") (pin "2") (pinfunction "2_2") (pintype "passive"))
      (node (ref "R4") (pin "P$2") (pinfunction "P$2_P$2") (pintype "passive"))
      (node (ref "U1") (pin "45") (pinfunction "PB8-BOOT0_45") (pintype "bidirectional"))
    )
    (net (code "29") (name "/I2C_ABS_SDA") (class "Default")
      (node (ref "ABS") (pin "3") (pinfunction "3_3") (pintype "passive"))
      (node (ref "R3") (pin "P$2") (pinfunction "P$2_P$2") (pintype "passive"))
      (node (ref "U1") (pin "46") (pinfunction "PB9_46") (pintype "bidirectional"))
    )
    (net (code "30") (name "/LED1") (class "Default")
      (node (ref "D3") (pin "CATHODE") (pinfunction "CATHODE_CATHODE") (pintype "power_in"))
      (node (ref "U1") (pin "4") (pinfunction "PC15-OSC32_OUT_4") (pintype "bidirectional"))
    )
    (net (code "31") (name "/LED2") (class "Default")
      (node (ref "D2") (pin "CATHODE") (pinfunction "CATHODE_CATHODE") (pintype "power_in"))
      (node (ref "U1") (pin "3") (pinfunction "PC14-OSC32_IN_3") (pintype "bidirectional"))
    )
    (net (code "32") (name "/MOTOR1") (class "Default")
      (node (ref "MOT1") (pin "P$1") (pinfunction "P$1_P$1") (pintype "bidirectional"))
      (node (ref "U1") (pin "8") (pinfunction "PA0_8") (pintype "bidirectional"))
      (node (ref "U4") (pin "37") (pinfunction "INHA_37") (pintype "bidirectional"))
    )
    (net (code "33") (name "/MOTOR2") (class "Default")
      (node (ref "MOT2") (pin "P$1") (pinfunction "P$1_P$1") (pintype "bidirectional"))
      (node (ref "U1") (pin "9") (pinfunction "PA1_9") (pintype "bidirectional"))
      (node (ref "U4") (pin "39") (pinfunction "INHB_39") (pintype "bidirectional"))
    )
    (net (code "34") (name "/MOTOR3") (class "Default")
      (node (ref "MOT3") (pin "P$1") (pinfunction "P$1_P$1") (pintype "bidirectional"))
      (node (ref "U1") (pin "10") (pinfunction "PA2_10") (pintype "bidirectional"))
      (node (ref "U4") (pin "41") (pinfunction "INHC_41") (pintype "bidirectional"))
    )
    (net (code "35") (name "/MOTOR_ENABLE") (class "Default")
      (node (ref "U1") (pin "11") (pinfunction "PA3_11") (pintype "bidirectional"))
      (node (ref "U4") (pin "33") (pinfunction "ENABLE_33") (pintype "bidirectional"))
    )
    (net (code "36") (name "/MOTOR_FAULT") (class "Default")
      (node (ref "U1") (pin "43") (pinfunction "PB6_43") (pintype "bidirectional"))
      (node (ref "U4") (pin "28") (pinfunction "FAULT_28") (pintype "bidirectional"))
    )
    (net (code "37") (name "/MOTOR_HIZ") (class "Default")
      (node (ref "U1") (pin "44") (pinfunction "PB7_44") (pintype "bidirectional"))
      (node (ref "U4") (pin "38") (pinfunction "INLA_38") (pintype "bidirectional"))
      (node (ref "U4") (pin "40") (pinfunction "INLB_40") (pintype "bidirectional"))
      (node (ref "U4") (pin "42") (pinfunction "INLC_42") (pintype "bidirectional"))
    )
    (net (code "38") (name "/NRST") (class "Default")
      (node (ref "C3") (pin "P$1") (pinfunction "P$1_P$1") (pintype "passive"))
      (node (ref "SWD") (pin "2") (pinfunction "2_2") (pintype "passive"))
      (node (ref "U1") (pin "7") (pinfunction "PG10-NRST_7") (pintype "bidirectional"))
    )
    (net (code "39") (name "/SHA") (class "Default")
      (node (ref "A") (pin "1") (pinfunction "P$1_1") (pintype "bidirectional"))
      (node (ref "DA") (pin "P$1") (pinfunction "P$1_P$1") (pintype "bidirectional"))
      (node (ref "Q1") (pin "1") (pinfunction "S_1") (pintype "passive"))
      (node (ref "Q1") (pin "2") (pinfunction "S_2") (pintype "passive"))
      (node (ref "Q1") (pin "3") (pinfunction "S_3") (pintype "passive"))
      (node (ref "Q2") (pin "5") (pinfunction "D_5") (pintype "passive"))
      (node (ref "Q2") (pin "6") (pinfunction "D_6") (pintype "passive"))
      (node (ref "Q2") (pin "7") (pinfunction "D_7") (pintype "passive"))
      (node (ref "Q2") (pin "8") (pinfunction "D_8") (pintype "passive"))
      (node (ref "Q2") (pin "PAD") (pinfunction "D_PAD") (pintype "passive"))
      (node (ref "U4") (pin "9") (pinfunction "SHA_9") (pintype "bidirectional"))
    )
    (net (code "40") (name "/SHB") (class "Default")
      (node (ref "B") (pin "1") (pinfunction "P$1_1") (pintype "bidirectional"))
      (node (ref "DB") (pin "P$1") (pinfunction "P$1_P$1") (pintype "bidirectional"))
      (node (ref "Q3") (pin "1") (pinfunction "S_1") (pintype "passive"))
      (node (ref "Q3") (pin "2") (pinfunction "S_2") (pintype "passive"))
      (node (ref "Q3") (pin "3") (pinfunction "S_3") (pintype "passive"))
      (node (ref "Q4") (pin "5") (pinfunction "D_5") (pintype "passive"))
      (node (ref "Q4") (pin "6") (pinfunction "D_6") (pintype "passive"))
      (node (ref "Q4") (pin "7") (pinfunction "D_7") (pintype "passive"))
      (node (ref "Q4") (pin "8") (pinfunction "D_8") (pintype "passive"))
      (node (ref "Q4") (pin "PAD") (pinfunction "D_PAD") (pintype "passive"))
      (node (ref "U4") (pin "16") (pinfunction "SHB_16") (pintype "bidirectional"))
    )
    (net (code "41") (name "/SHC") (class "Default")
      (node (ref "C") (pin "1") (pinfunction "P$1_1") (pintype "bidirectional"))
      (node (ref "DC") (pin "P$1") (pinfunction "P$1_P$1") (pintype "bidirectional"))
      (node (ref "Q5") (pin "1") (pinfunction "S_1") (pintype "passive"))
      (node (ref "Q5") (pin "2") (pinfunction "S_2") (pintype "passive"))
      (node (ref "Q5") (pin "3") (pinfunction "S_3") (pintype "passive"))
      (node (ref "Q6") (pin "5") (pinfunction "D_5") (pintype "passive"))
      (node (ref "Q6") (pin "6") (pinfunction "D_6") (pintype "passive"))
      (node (ref "Q6") (pin "7") (pinfunction "D_7") (pintype "passive"))
      (node (ref "Q6") (pin "8") (pinfunction "D_8") (pintype "passive"))
      (node (ref "Q6") (pin "PAD") (pinfunction "D_PAD") (pintype "passive"))
      (node (ref "U4") (pin "19") (pinfunction "SHC_19") (pintype "bidirectional"))
    )
    (net (code "42") (name "/SNA") (class "Default")
      (node (ref "SH1") (pin "1") (pinfunction "P$1_1") (pintype "bidirectional"))
      (node (ref "U4") (pin "12") (pinfunction "SNA_12") (pintype "bidirectional"))
    )
    (net (code "43") (name "/SNB") (class "Default")
      (node (ref "SH2") (pin "1") (pinfunction "P$1_1") (pintype "bidirectional"))
      (node (ref "U4") (pin "13") (pinfunction "SNB_13") (pintype "bidirectional"))
    )
    (net (code "44") (name "/SNC") (class "Default")
      (node (ref "SH3") (pin "1") (pinfunction "P$1_1") (pintype "bidirectional"))
      (node (ref "U4") (pin "22") (pinfunction "SNC_22") (pintype "bidirectional"))
    )
    (net (code "45") (name "/SPA") (class "Default")
      (node (ref "Q2") (pin "1") (pinfunction "S_1") (pintype "passive"))
      (node (ref "Q2") (pin "2") (pinfunction "S_2") (pintype "passive"))
      (node (ref "Q2") (pin "3") (pinfunction "S_3") (pintype "passive"))
      (node (ref "RA") (pin "2") (pinfunction "2_2") (pintype "passive"))
      (node (ref "U4") (pin "11") (pinfunction "SPA_11") (pintype "bidirectional"))
    )
    (net (code "46") (name "/SPB") (class "Default")
      (node (ref "Q4") (pin "1") (pinfunction "S_1") (pintype "passive"))
      (node (ref "Q4") (pin "2") (pinfunction "S_2") (pintype "passive"))
      (node (ref "Q4") (pin "3") (pinfunction "S_3") (pintype "passive"))
      (node (ref "RB") (pin "2") (pinfunction "2_2") (pintype "passive"))
      (node (ref "U4") (pin "14") (pinfunction "SPB_14") (pintype "bidirectional"))
    )
    (net (code "47") (name "/SPC") (class "Default")
      (node (ref "Q6") (pin "1") (pinfunction "S_1") (pintype "passive"))
      (node (ref "Q6") (pin "2") (pinfunction "S_2") (pintype "passive"))
      (node (ref "Q6") (pin "3") (pinfunction "S_3") (pintype "passive"))
      (node (ref "RC") (pin "2") (pinfunction "2_2") (pintype "passive"))
      (node (ref "U4") (pin "21") (pinfunction "SPC_21") (pintype "bidirectional"))
    )
    (net (code "48") (name "/SWCLK") (class "Default")
      (node (ref "SWD") (pin "5") (pinfunction "5_5") (pintype "passive"))
      (node (ref "U1") (pin "38") (pinfunction "PA14_38") (pintype "bidirectional"))
    )
    (net (code "49") (name "/SWDIO") (class "Default")
      (node (ref "SWD") (pin "3") (pinfunction "3_3") (pintype "passive"))
      (node (ref "U1") (pin "37") (pinfunction "PA13_37") (pintype "bidirectional"))
    )
    (net (code "50") (name "/VBAT_SENSE") (class "Default")
      (node (ref "R5") (pin "P$1") (pinfunction "P$1_P$1") (pintype "passive"))
      (node (ref "R6") (pin "P$2") (pinfunction "P$2_P$2") (pintype "passive"))
      (node (ref "U1") (pin "30") (pinfunction "PA8_30") (pintype "bidirectional"))
    )
    (net (code "51") (name "/VTEMP_FET") (class "Default")
      (node (ref "C13") (pin "P$1") (pinfunction "P$1_P$1") (pintype "passive"))
      (node (ref "R8") (pin "P$2") (pinfunction "P$2_P$2") (pintype "passive"))
      (node (ref "R9") (pin "P$1") (pinfunction "P$1_P$1") (pintype "passive"))
      (node (ref "U1") (pin "31") (pinfunction "PA9_31") (pintype "bidirectional"))
    )
    (net (code "52") (name "/VTEMP_MOT") (class "Default")
      (node (ref "R7") (pin "P$1") (pinfunction "P$1_P$1") (pintype "passive"))
      (node (ref "TEMP2") (pin "P$1") (pinfunction "P$1_P$1") (pintype "bidirectional"))
      (node (ref "U1") (pin "26") (pinfunction "PB12_26") (pintype "bidirectional"))
    )
    (net (code "53") (name "GND") (class "Default")
      (node (ref "ABS") (pin "4") (pinfunction "4_4") (pintype "passive"))
      (node (ref "C1") (pin "P$2") (pinfunction "P$2_P$2") (pintype "passive"))
      (node (ref "C10") (pin "P$2") (pinfunction "P$2_P$2") (pintype "passive"))
      (node (ref "C11") (pin "P$2") (pinfunction "P$2_P$2") (pintype "passive"))
      (node (ref "C12") (pin "P$2") (pinfunction "P$2_P$2") (pintype "passive"))
      (node (ref "C13") (pin "P$2") (pinfunction "P$2_P$2") (pintype "passive"))
      (node (ref "C17") (pin "P$1") (pinfunction "P$1_P$1") (pintype "passive"))
      (node (ref "C18") (pin "P$1") (pinfunction "P$1_P$1") (pintype "passive"))
      (node (ref "C2") (pin "P$2") (pinfunction "P$2_P$2") (pintype "passive"))
      (node (ref "C21") (pin "P$2") (pinfunction "P$2_P$2") (pintype "passive"))
      (node (ref "C3") (pin "P$2") (pinfunction "P$2_P$2") (pintype "passive"))
      (node (ref "C4") (pin "P$2") (pinfunction "P$2_P$2") (pintype "passive"))
      (node (ref "C5") (pin "P$2") (pinfunction "P$2_P$2") (pintype "passive"))
      (node (ref "C6") (pin "P$2") (pinfunction "P$2_P$2") (pintype "passive"))
      (node (ref "C7") (pin "P$1") (pinfunction "P$1_P$1") (pintype "passive"))
      (node (ref "C8") (pin "P$2") (pinfunction "P$2_P$2") (pintype "passive"))
      (node (ref "C9") (pin "P$2") (pinfunction "P$2_P$2") (pintype "passive"))
      (node (ref "CAN1") (pin "3") (pinfunction "3_3") (pintype "passive"))
      (node (ref "CAN2") (pin "3") (pinfunction "3_3") (pintype "passive"))
      (node (ref "DG1") (pin "P$1") (pinfunction "P$1_P$1") (pintype "bidirectional"))
      (node (ref "DG2") (pin "P$1") (pinfunction "P$1_P$1") (pintype "bidirectional"))
      (node (ref "R6") (pin "P$1") (pinfunction "P$1_P$1") (pintype "passive"))
      (node (ref "R7") (pin "P$2") (pinfunction "P$2_P$2") (pintype "passive"))
      (node (ref "R9") (pin "P$2") (pinfunction "P$2_P$2") (pintype "passive"))
      (node (ref "SH4") (pin "2") (pinfunction "P$2_2") (pintype "bidirectional"))
      (node (ref "SWD") (pin "4") (pinfunction "4_4") (pintype "passive"))
      (node (ref "U1") (pin "19") (pinfunction "VSSA_19") (pintype "bidirectional"))
      (node (ref "U1") (pin "23") (pinfunction "VSS_1_23") (pintype "bidirectional"))
      (node (ref "U1") (pin "35") (pinfunction "VSS_2_35") (pintype "bidirectional"))
      (node (ref "U1") (pin "47") (pinfunction "VSS_3_47") (pintype "bidirectional"))
      (node (ref "U1") (pin "49") (pinfunction "THERMALPAD_49") (pintype "bidirectional"))
      (node (ref "U2") (pin "2") (pinfunction "GND_2") (pintype "power_in"))
      (node (ref "U2") (pin "5") (pinfunction "SHDN_5") (pintype "input"))
      (node (ref "U2") (pin "8") (pinfunction "STB_8") (pintype "input"))
      (node (ref "U3") (pin "13") (pinfunction "GND_13") (pintype "bidirectional"))
      (node (ref "U3") (pin "5") (pinfunction "TEST_5") (pintype "bidirectional"))
      (node (ref "U4") (pin "27") (pinfunction "DGND_27") (pintype "bidirectional"))
      (node (ref "U4") (pin "35") (pinfunction "AGND_35") (pintype "bidirectional"))
    )
    (net (code "54") (name "Net-(D2-PadANODE)") (class "Default")
      (node (ref "D2") (pin "ANODE") (pinfunction "ANODE_ANODE") (pintype "power_in"))
      (node (ref "R2") (pin "P$2") (pinfunction "P$2_P$2") (pintype "passive"))
    )
    (net (code "55") (name "Net-(D3-PadANODE)") (class "Default")
      (node (ref "D3") (pin "ANODE") (pinfunction "ANODE_ANODE") (pintype "power_in"))
      (node (ref "R1") (pin "P$2") (pinfunction "P$2_P$2") (pintype "passive"))
    )
    (net (code "56") (name "Net-(U2-CANH)") (class "Default")
      (node (ref "CAN1") (pin "1") (pinfunction "1_1") (pintype "passive"))
      (node (ref "CAN2") (pin "1") (pinfunction "1_1") (pintype "passive"))
      (node (ref "U2") (pin "7") (pinfunction "CANH_7") (pintype "bidirectional"))
    )
    (net (code "57") (name "Net-(U2-CANL)") (class "Default")
      (node (ref "CAN1") (pin "2") (pinfunction "2_2") (pintype "passive"))
      (node (ref "CAN2") (pin "2") (pinfunction "2_2") (pintype "passive"))
      (node (ref "U2") (pin "6") (pinfunction "CANL_6") (pintype "bidirectional"))
    )
    (net (code "58") (name "Net-(U4-CB)") (class "Default")
      (node (ref "C20") (pin "P$1") (pinfunction "P$1_P$1") (pintype "passive"))
      (node (ref "U4") (pin "44") (pinfunction "CB_44") (pintype "bidirectional"))
    )
    (net (code "59") (name "Net-(U4-CPH)") (class "Default")
      (node (ref "C16") (pin "P$1") (pinfunction "P$1_P$1") (pintype "passive"))
      (node (ref "U4") (pin "4") (pinfunction "CPH_4") (pintype "bidirectional"))
    )
    (net (code "60") (name "Net-(U4-CPL)") (class "Default")
      (node (ref "C16") (pin "P$2") (pinfunction "P$2_P$2") (pintype "passive"))
      (node (ref "U4") (pin "3") (pinfunction "CPL_3") (pintype "bidirectional"))
    )
    (net (code "61") (name "Net-(U4-DVDD)") (class "Default")
      (node (ref "C17") (pin "P$2") (pinfunction "P$2_P$2") (pintype "passive"))
      (node (ref "U4") (pin "36") (pinfunction "DVDD_36") (pintype "bidirectional"))
    )
    (net (code "62") (name "Net-(U4-FB)") (class "Default")
      (node (ref "R11") (pin "P$2") (pinfunction "P$2_P$2") (pintype "passive"))
      (node (ref "R12") (pin "P$1") (pinfunction "P$1_P$1") (pintype "passive"))
      (node (ref "U4") (pin "1") (pinfunction "FB_1") (pintype "bidirectional"))
    )
    (net (code "63") (name "Net-(U4-SHDN)") (class "Default")
      (node (ref "R10") (pin "P$1") (pinfunction "P$1_P$1") (pintype "passive"))
      (node (ref "U4") (pin "48") (pinfunction "SHDN_48") (pintype "bidirectional"))
    )
    (net (code "64") (name "Net-(U4-SW)") (class "Default")
      (node (ref "C20") (pin "P$2") (pinfunction "P$2_P$2") (pintype "passive"))
      (node (ref "D1") (pin "CATHODE") (pinfunction "CATHODE_CATHODE") (pintype "bidirectional"))
      (node (ref "L1") (pin "2") (pinfunction "2_2") (pintype "passive"))
      (node (ref "U4") (pin "45") (pinfunction "SW_45") (pintype "bidirectional"))
    )
    (net (code "65") (name "Net-(U4-VCP)") (class "Default")
      (node (ref "C15") (pin "P$2") (pinfunction "P$2_P$2") (pintype "passive"))
      (node (ref "U4") (pin "5") (pinfunction "VCP_5") (pintype "bidirectional"))
    )
    (net (code "66") (name "V+") (class "Default")
      (node (ref "C14") (pin "P$1") (pinfunction "P$1_P$1") (pintype "passive"))
      (node (ref "C15") (pin "P$1") (pinfunction "P$1_P$1") (pintype "passive"))
      (node (ref "C19") (pin "P$1") (pinfunction "P$1_P$1") (pintype "passive"))
      (node (ref "C22") (pin "P$1") (pinfunction "P$1_P$1") (pintype "passive"))
      (node (ref "C23") (pin "P$1") (pinfunction "P$1_P$1") (pintype "passive"))
      (node (ref "C24") (pin "P$1") (pinfunction "P$1_P$1") (pintype "passive"))
      (node (ref "C25") (pin "P$1") (pinfunction "P$1_P$1") (pintype "passive"))
      (node (ref "C26") (pin "P$1") (pinfunction "P$1_P$1") (pintype "passive"))
      (node (ref "C27") (pin "P$1") (pinfunction "P$1_P$1") (pintype "passive"))
      (node (ref "C28") (pin "P$1") (pinfunction "P$1_P$1") (pintype "passive"))
      (node (ref "C29") (pin "P$1") (pinfunction "P$1_P$1") (pintype "passive"))
      (node (ref "C30") (pin "P$1") (pinfunction "P$1_P$1") (pintype "passive"))
      (node (ref "C31") (pin "P$1") (pinfunction "P$1_P$1") (pintype "passive"))
      (node (ref "C32") (pin "P$1") (pinfunction "P$1_P$1") (pintype "passive"))
      (node (ref "C33") (pin "P$1") (pinfunction "P$1_P$1") (pintype "passive"))
      (node (ref "C34") (pin "P$1") (pinfunction "P$1_P$1") (pintype "passive"))
      (node (ref "C35") (pin "P$1") (pinfunction "P$1_P$1") (pintype "passive"))
      (node (ref "C36") (pin "P$1") (pinfunction "P$1_P$1") (pintype "passive"))
      (node (ref "C37") (pin "P$1") (pinfunction "P$1_P$1") (pintype "passive"))
      (node (ref "J1") (pin "1") (pinfunction "1_1") (pintype "passive"))
      (node (ref "J2") (pin "1") (pinfunction "1_1") (pintype "passive"))
      (node (ref "Q1") (pin "5") (pinfunction "D_5") (pintype "passive"))
      (node (ref "Q1") (pin "6") (pinfunction "D_6") (pintype "passive"))
      (node (ref "Q1") (pin "7") (pinfunction "D_7") (pintype "passive"))
      (node (ref "Q1") (pin "8") (pinfunction "D_8") (pintype "passive"))
      (node (ref "Q1") (pin "PAD") (pinfunction "D_PAD") (pintype "passive"))
      (node (ref "Q3") (pin "5") (pinfunction "D_5") (pintype "passive"))
      (node (ref "Q3") (pin "6") (pinfunction "D_6") (pintype "passive"))
      (node (ref "Q3") (pin "7") (pinfunction "D_7") (pintype "passive"))
      (node (ref "Q3") (pin "8") (pinfunction "D_8") (pintype "passive"))
      (node (ref "Q3") (pin "PAD") (pinfunction "D_PAD") (pintype "passive"))
      (node (ref "Q5") (pin "5") (pinfunction "D_5") (pintype "passive"))
      (node (ref "Q5") (pin "6") (pinfunction "D_6") (pintype "passive"))
      (node (ref "Q5") (pin "7") (pinfunction "D_7") (pintype "passive"))
      (node (ref "Q5") (pin "8") (pinfunction "D_8") (pintype "passive"))
      (node (ref "Q5") (pin "PAD") (pinfunction "D_PAD") (pintype "passive"))
      (node (ref "R10") (pin "P$2") (pinfunction "P$2_P$2") (pintype "passive"))
      (node (ref "R5") (pin "P$2") (pinfunction "P$2_P$2") (pintype "passive"))
      (node (ref "U4") (pin "47") (pinfunction "VIN_47") (pintype "bidirectional"))
      (node (ref "U4") (pin "6") (pinfunction "VM_6") (pintype "bidirectional"))
      (node (ref "U4") (pin "7") (pinfunction "VDRAIN_7") (pintype "bidirectional"))
    )
    (net (code "67") (name "V-") (class "Default")
      (node (ref "C14") (pin "P$2") (pinfunction "P$2_P$2") (pintype "passive"))
      (node (ref "C19") (pin "P$2") (pinfunction "P$2_P$2") (pintype "passive"))
      (node (ref "C22") (pin "P$2") (pinfunction "P$2_P$2") (pintype "passive"))
      (node (ref "C23") (pin "P$2") (pinfunction "P$2_P$2") (pintype "passive"))
      (node (ref "C24") (pin "P$2") (pinfunction "P$2_P$2") (pintype "passive"))
      (node (ref "C25") (pin "P$2") (pinfunction "P$2_P$2") (pintype "passive"))
      (node (ref "C26") (pin "P$2") (pinfunction "P$2_P$2") (pintype "passive"))
      (node (ref "C27") (pin "P$2") (pinfunction "P$2_P$2") (pintype "passive"))
      (node (ref "C28") (pin "P$2") (pinfunction "P$2_P$2") (pintype "passive"))
      (node (ref "C29") (pin "P$2") (pinfunction "P$2_P$2") (pintype "passive"))
      (node (ref "C30") (pin "P$2") (pinfunction "P$2_P$2") (pintype "passive"))
      (node (ref "C31") (pin "P$2") (pinfunction "P$2_P$2") (pintype "passive"))
      (node (ref "C32") (pin "P$2") (pinfunction "P$2_P$2") (pintype "passive"))
      (node (ref "C33") (pin "P$2") (pinfunction "P$2_P$2") (pintype "passive"))
      (node (ref "C34") (pin "P$2") (pinfunction "P$2_P$2") (pintype "passive"))
      (node (ref "C35") (pin "P$2") (pinfunction "P$2_P$2") (pintype "passive"))
      (node (ref "C36") (pin "P$2") (pinfunction "P$2_P$2") (pintype "passive"))
      (node (ref "C37") (pin "P$2") (pinfunction "P$2_P$2") (pintype "passive"))
      (node (ref "D1") (pin "ANODE") (pinfunction "ANODE_ANODE") (pintype "bidirectional"))
      (node (ref "J1") (pin "2") (pinfunction "2_2") (pintype "passive"))
      (node (ref "J2") (pin "2") (pinfunction "2_2") (pintype "passive"))
      (node (ref "R12") (pin "P$2") (pinfunction "P$2_P$2") (pintype "passive"))
      (node (ref "RA") (pin "1") (pinfunction "1_1") (pintype "passive"))
      (node (ref "RB") (pin "1") (pinfunction "1_1") (pintype "passive"))
      (node (ref "RC") (pin "1") (pinfunction "1_1") (pintype "passive"))
      (node (ref "SH1") (pin "2") (pinfunction "P$2_2") (pintype "bidirectional"))
      (node (ref "SH2") (pin "2") (pinfunction "P$2_2") (pintype "bidirectional"))
      (node (ref "SH3") (pin "2") (pinfunction "P$2_2") (pintype "bidirectional"))
      (node (ref "SH4") (pin "1") (pinfunction "P$1_1") (pintype "bidirectional"))
      (node (ref "U4") (pin "2") (pinfunction "PGND_2") (pintype "bidirectional"))
      (node (ref "U4") (pin "43") (pinfunction "BGND_43") (pintype "bidirectional"))
      (node (ref "U4") (pin "P1") (pinfunction "PAD_P1") (pintype "bidirectional"))
      (node (ref "U4") (pin "P10") (pinfunction "PAD_P10") (pintype "bidirectional"))
      (node (ref "U4") (pin "P11") (pinfunction "PAD_P11") (pintype "bidirectional"))
      (node (ref "U4") (pin "P12") (pinfunction "PAD_P12") (pintype "bidirectional"))
      (node (ref "U4") (pin "P13") (pinfunction "PAD_P13") (pintype "bidirectional"))
      (node (ref "U4") (pin "P14") (pinfunction "PAD_P14") (pintype "bidirectional"))
      (node (ref "U4") (pin "P15") (pinfunction "PAD_P15") (pintype "bidirectional"))
      (node (ref "U4") (pin "P16") (pinfunction "PAD_P16") (pintype "bidirectional"))
      (node (ref "U4") (pin "P17") (pinfunction "PAD_P17") (pintype "bidirectional"))
      (node (ref "U4") (pin "P18") (pinfunction "PAD_P18") (pintype "bidirectional"))
      (node (ref "U4") (pin "P19") (pinfunction "PAD_P19") (pintype "bidirectional"))
      (node (ref "U4") (pin "P2") (pinfunction "PAD_P2") (pintype "bidirectional"))
      (node (ref "U4") (pin "P20") (pinfunction "PAD_P20") (pintype "bidirectional"))
      (node (ref "U4") (pin "P21") (pinfunction "PAD_P21") (pintype "bidirectional"))
      (node (ref "U4") (pin "P22") (pinfunction "PAD_P22") (pintype "bidirectional"))
      (node (ref "U4") (pin "P23") (pinfunction "PAD_P23") (pintype "bidirectional"))
      (node (ref "U4") (pin "P24") (pinfunction "PAD_P24") (pintype "bidirectional"))
      (node (ref "U4") (pin "P25") (pinfunction "PAD_P25") (pintype "bidirectional"))
      (node (ref "U4") (pin "P3") (pinfunction "PAD_P3") (pintype "bidirectional"))
      (node (ref "U4") (pin "P4") (pinfunction "PAD_P4") (pintype "bidirectional"))
      (node (ref "U4") (pin "P5") (pinfunction "PAD_P5") (pintype "bidirectional"))
      (node (ref "U4") (pin "P6") (pinfunction "PAD_P6") (pintype "bidirectional"))
      (node (ref "U4") (pin "P7") (pinfunction "PAD_P7") (pintype "bidirectional"))
      (node (ref "U4") (pin "P8") (pinfunction "PAD_P8") (pintype "bidirectional"))
      (node (ref "U4") (pin "P9") (pinfunction "PAD_P9") (pintype "bidirectional"))
      (node (ref "U4") (pin "PAD") (pinfunction "PAD_PAD") (pintype "bidirectional"))
    )
    (net (code "68") (name "unconnected-(SWD-Pad1)") (class "Default")
      (node (ref "SWD") (pin "1") (pinfunction "1_1") (pintype "passive"))
    )
    (net (code "69") (name "unconnected-(U1-PA10-Pad32)") (class "Default")
      (node (ref "U1") (pin "32") (pinfunction "PA10_32") (pintype "bidirectional"))
    )
    (net (code "70") (name "unconnected-(U1-PB10-Pad22)") (class "Default")
      (node (ref "U1") (pin "22") (pinfunction "PB10_22") (pintype "bidirectional"))
    )
    (net (code "71") (name "unconnected-(U1-VBAT-Pad1)") (class "Default")
      (node (ref "U1") (pin "1") (pinfunction "VBAT_1") (pintype "bidirectional"))
    )
    (net (code "72") (name "unconnected-(U3-I-Pad14)") (class "Default")
      (node (ref "U3") (pin "14") (pinfunction "I_14") (pintype "bidirectional"))
    )
    (net (code "73") (name "unconnected-(U3-PWM-Pad8)") (class "Default")
      (node (ref "U3") (pin "8") (pinfunction "PWM_8") (pintype "bidirectional"))
    )
    (net (code "74") (name "unconnected-(U3-VDD5V-Pad11)") (class "Default")
      (node (ref "U3") (pin "11") (pinfunction "VDD5V_11") (pintype "bidirectional"))
    )
    (net (code "75") (name "unconnected-(U4-CAL-Pad34)") (class "Default")
      (node (ref "U4") (pin "34") (pinfunction "CAL_34") (pintype "bidirectional"))
    )
  )
)
